# esp.net
KiCad netlist of a schematic drawn in Altium Designer
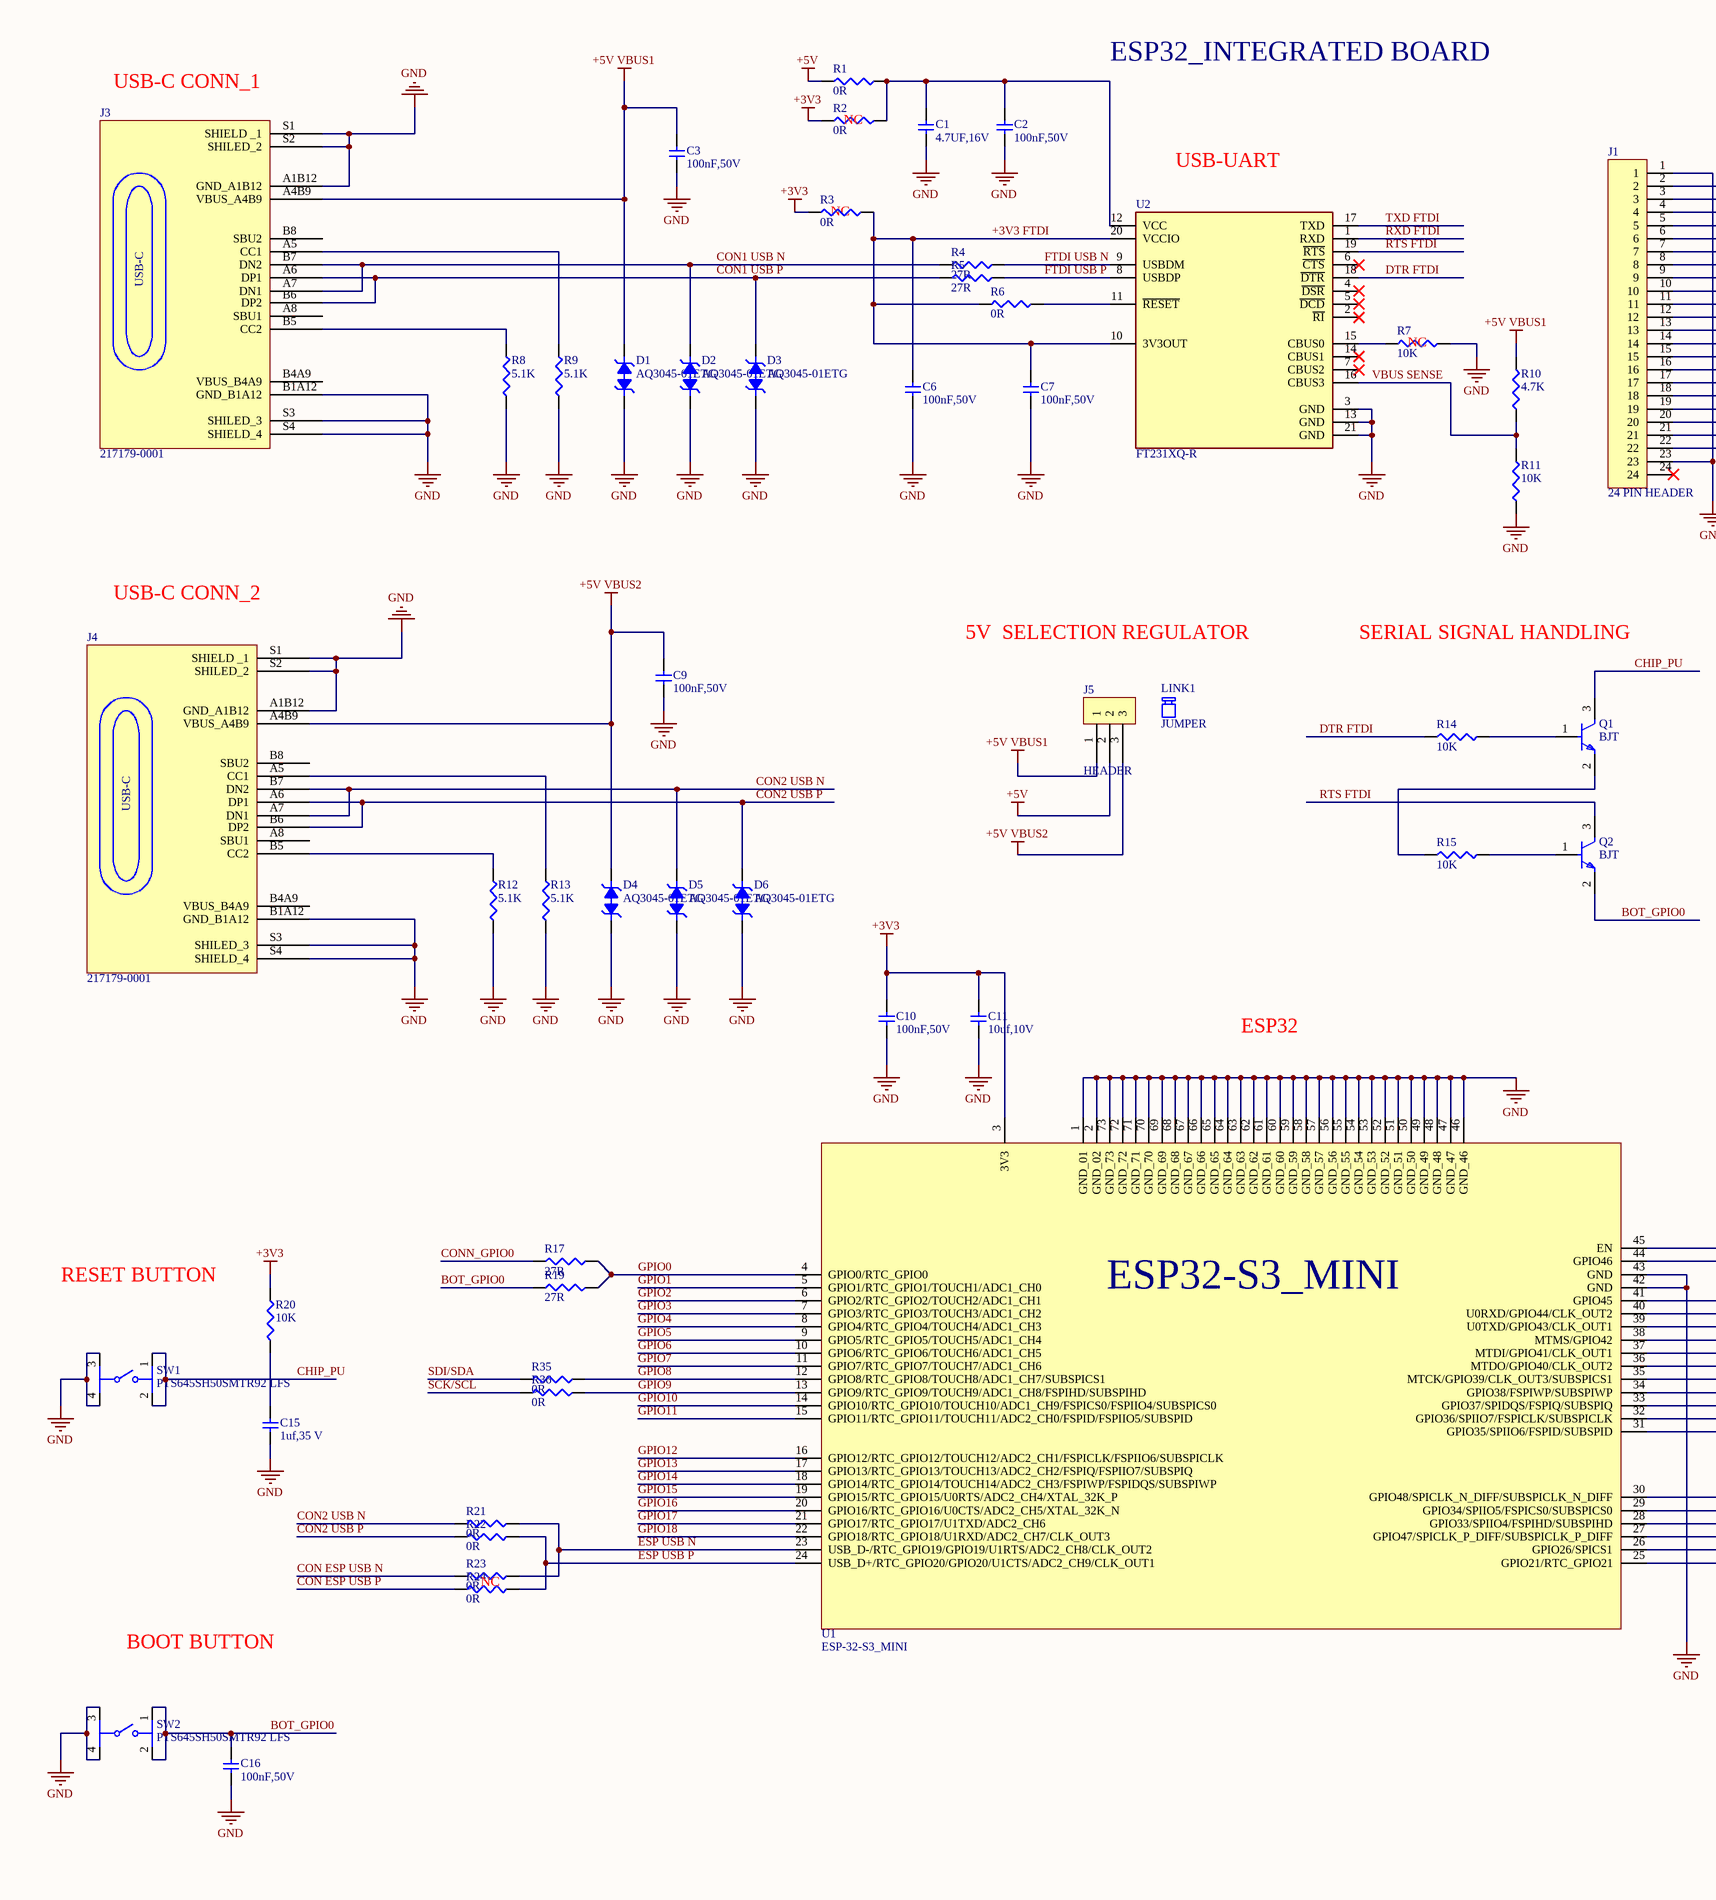
[diagram p0: esp.SchDoc, left]
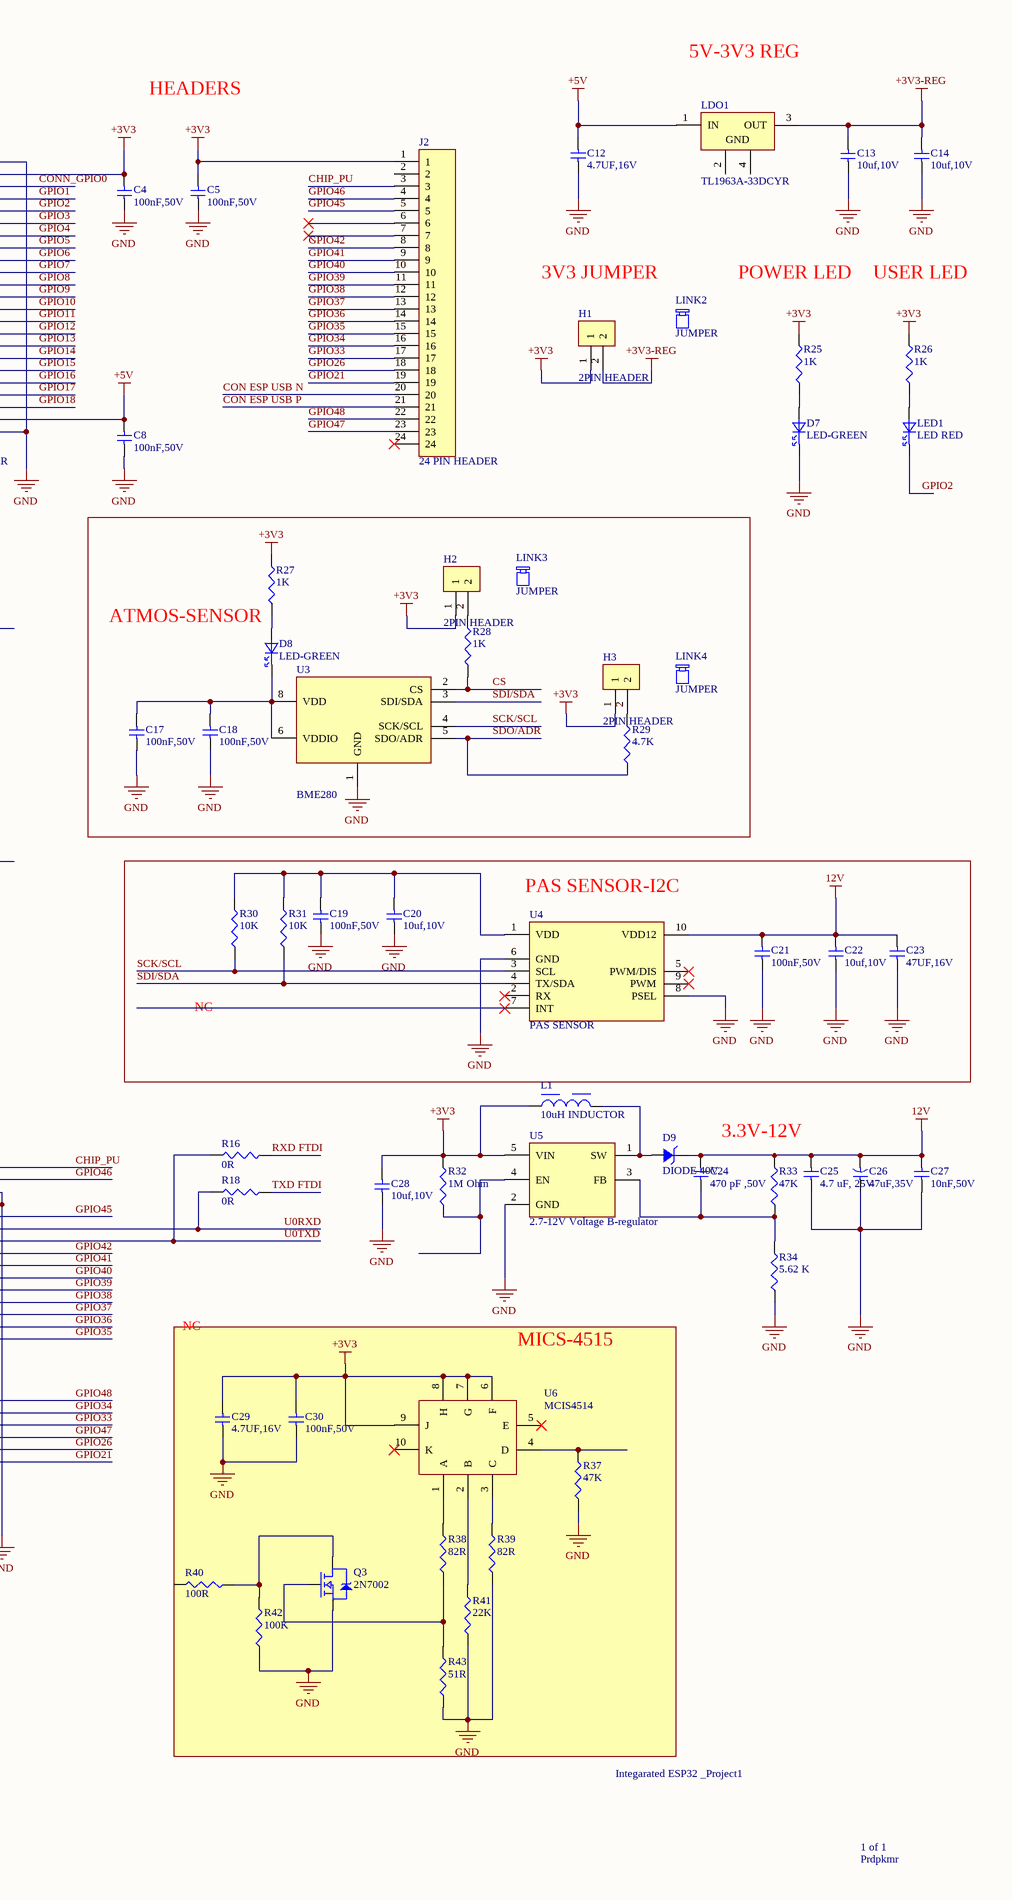
[diagram p1: esp.SchDoc, right]

(export (version "E")
  (design (tool "Eeschema 10.0.6"))
  (components
    (comp (ref "C1")
      (value "4.7UF,16V")
      (footprint "CAPC1005X55N")
      (description "CAP CER 4.7UF 6.3V X5R 0402")
      (fields
        (field (name "MANUFACTURER") "Samsung")
        (field (name "MANUFACTURER PART NUMBER") "CL05A475KQ5NRNC")
      )
      (libsource (lib "Schlib1") (part "CL05A475KQ5NRNC"))
    )
    (comp (ref "C2")
      (value "100nF,50V")
      (footprint "CAPC1005X55N")
      (description "CL05B104KB54PNC")
      (fields (field (name "MANUFACTURER") "Samsung") (field (name "TOLERANCE") "10%"))
      (libsource (lib "Schlib1") (part "CL05B104KB54PNC"))
    )
    (comp (ref "C3")
      (value "100nF,50V")
      (footprint "CAPC1005X55N")
      (description "CL05B104KB54PNC")
      (fields (field (name "MANUFACTURER") "Samsung") (field (name "TOLERANCE") "10%"))
      (libsource (lib "Schlib1") (part "CL05B104KB54PNC"))
    )
    (comp (ref "C4")
      (value "100nF,50V")
      (footprint "CAPC1005X55N")
      (description "CL05B104KB54PNC")
      (fields (field (name "MANUFACTURER") "Samsung") (field (name "TOLERANCE") "10%"))
      (libsource (lib "Schlib1") (part "CL05B104KB54PNC"))
    )
    (comp (ref "C5")
      (value "100nF,50V")
      (footprint "CAPC1005X55N")
      (description "CL05B104KB54PNC")
      (fields (field (name "MANUFACTURER") "Samsung") (field (name "TOLERANCE") "10%"))
      (libsource (lib "Schlib1") (part "CL05B104KB54PNC"))
    )
    (comp (ref "C6")
      (value "100nF,50V")
      (footprint "CAPC1005X55N")
      (description "CL05B104KB54PNC")
      (fields (field (name "MANUFACTURER") "Samsung") (field (name "TOLERANCE") "10%"))
      (libsource (lib "Schlib1") (part "CL05B104KB54PNC"))
    )
    (comp (ref "C7")
      (value "100nF,50V")
      (footprint "CAPC1005X55N")
      (description "CL05B104KB54PNC")
      (fields (field (name "MANUFACTURER") "Samsung") (field (name "TOLERANCE") "10%"))
      (libsource (lib "Schlib1") (part "CL05B104KB54PNC"))
    )
    (comp (ref "C8")
      (value "100nF,50V")
      (footprint "CAPC1005X55N")
      (description "CL05B104KB54PNC")
      (fields (field (name "MANUFACTURER") "Samsung") (field (name "TOLERANCE") "10%"))
      (libsource (lib "Schlib1") (part "CL05B104KB54PNC"))
    )
    (comp (ref "C9")
      (value "100nF,50V")
      (footprint "CAPC1005X55N")
      (description "CL05B104KB54PNC")
      (fields (field (name "MANUFACTURER") "Samsung") (field (name "TOLERANCE") "10%"))
      (libsource (lib "Schlib1") (part "CL05B104KB54PNC"))
    )
    (comp (ref "C10")
      (value "100nF,50V")
      (footprint "CAPC1005X55N")
      (description "CL05B104KB54PNC")
      (fields (field (name "MANUFACTURER") "Samsung") (field (name "TOLERANCE") "10%"))
      (libsource (lib "Schlib1") (part "CL05B104KB54PNC"))
    )
    (comp (ref "C11")
      (value "10uf,10V")
      (footprint "CAPC1005X55N")
      (description "CL05A106MP5NRNC")
      (fields (field (name "MANUFACTURER") "Samsung") (field (name "TOLERANCE") "20%"))
      (libsource (lib "Schlib1") (part "CL05A106MP5NRNC"))
    )
    (comp (ref "C12")
      (value "4.7UF,16V")
      (footprint "CAPC1005X55N")
      (description "CAP CER 4.7UF 6.3V X5R 0402")
      (fields
        (field (name "MANUFACTURER") "Samsung")
        (field (name "MANUFACTURER PART NUMBER") "CL05A475KQ5NRNC")
      )
      (libsource (lib "Schlib1") (part "CL05A475KQ5NRNC"))
    )
    (comp (ref "C13")
      (value "10uf,10V")
      (footprint "CAPC1005X55N")
      (description "CL05A106MP5NRNC")
      (fields (field (name "MANUFACTURER") "Samsung") (field (name "TOLERANCE") "20%"))
      (libsource (lib "Schlib1") (part "CL05A106MP5NRNC"))
    )
    (comp (ref "C14")
      (value "10uf,10V")
      (footprint "CAPC1005X55N")
      (description "CL05A106MP5NRNC")
      (fields (field (name "MANUFACTURER") "Samsung") (field (name "TOLERANCE") "20%"))
      (libsource (lib "Schlib1") (part "CL05A106MP5NRNC"))
    )
    (comp (ref "C15")
      (value "1uf,35 V")
      (footprint "CAPC1005X55N")
      (description "CL05A105KL5NRNC")
      (fields (field (name "MANUFACTURER") "Samsung") (field (name "TOLERANCE") "10%"))
      (libsource (lib "Schlib1") (part "CL05A105KL5NRNC"))
    )
    (comp (ref "C16")
      (value "100nF,50V")
      (footprint "CAPC1005X55N")
      (description "CL05B104KB54PNC")
      (fields (field (name "MANUFACTURER") "Samsung") (field (name "TOLERANCE") "10%"))
      (libsource (lib "Schlib1") (part "CL05B104KB54PNC"))
    )
    (comp (ref "C17")
      (value "100nF,50V")
      (footprint "CAPC1005X55N")
      (description "CL05B104KB54PNC")
      (fields (field (name "MANUFACTURER") "Samsung") (field (name "TOLERANCE") "10%"))
      (libsource (lib "Schlib1") (part "CL05B104KB54PNC"))
    )
    (comp (ref "C18")
      (value "100nF,50V")
      (footprint "CAPC1005X55N")
      (description "CL05B104KB54PNC")
      (fields (field (name "MANUFACTURER") "Samsung") (field (name "TOLERANCE") "10%"))
      (libsource (lib "Schlib1") (part "CL05B104KB54PNC"))
    )
    (comp (ref "C19")
      (value "100nF,50V")
      (footprint "CAPC1005X55N")
      (description "CL05B104KB54PNC")
      (fields (field (name "MANUFACTURER") "Samsung") (field (name "TOLERANCE") "10%"))
      (libsource (lib "Schlib1") (part "CL05B104KB54PNC"))
    )
    (comp (ref "C20")
      (value "10uf,10V")
      (footprint "CAPC1005X55N")
      (description "CL05A106MP5NRNC")
      (fields (field (name "MANUFACTURER") "Samsung") (field (name "TOLERANCE") "20%"))
      (libsource (lib "Schlib1") (part "CL05A106MP5NRNC"))
    )
    (comp (ref "C21")
      (value "100nF,50V")
      (footprint "CAPC1005X55N")
      (description "CL05B104KB54PNC")
      (fields (field (name "MANUFACTURER") "Samsung") (field (name "TOLERANCE") "10%"))
      (libsource (lib "Schlib1") (part "CL05B104KB54PNC"))
    )
    (comp (ref "C22")
      (value "10uf,10V")
      (footprint "CAPC1005X55N")
      (description "CL05A106MP5NRNC")
      (fields (field (name "MANUFACTURER") "Samsung") (field (name "TOLERANCE") "20%"))
      (libsource (lib "Schlib1") (part "CL05A106MP5NRNC"))
    )
    (comp (ref "C23")
      (value "47UF,16V")
      (footprint "CAPC1005X55N")
      (description "CAP TANT 47UF 10% 16V 2917")
      (fields
        (field (name "MANUFACTURER") "KEMET")
        (field (name "MANUFACTURER PART NUMBER") "T499D476K016ATE800")
      )
      (libsource (lib "Schlib1") (part "T499D476K016ATE800"))
    )
    (comp (ref "C24")
      (value "470 pF ,50V")
      (footprint "CAPC1005X55N")
      (description "CAP CER 470PF 50V C0G/NPO 0402")
      (fields
        (field (name "MANUFACTURER") "Yageo")
        (field (name "MANUFACTURER PART NUMBER") "CC0402FRNPO9BN471")
      )
      (libsource (lib "Schlib1") (part "CC0402FRNPO9BN471"))
    )
    (comp (ref "C25")
      (value "4.7 uF, 25V")
      (footprint "CAPC1005X55N")
      (description "Cap Cer 4.7UF 25V X5R 0402")
      (fields
        (field (name "MANUFACTURER") "Kyocera AVX")
        (field (name "MANUFACTURER PART NUMBER") "KGM05CR51E475MH")
      )
      (libsource (lib "Schlib1") (part "KGM05CR51E475MH"))
    )
    (comp (ref "C26")
      (value "47uF,35V")
      (description "CAP TANT 47UF 20% 35V 2917")
      (fields
        (field (name "MANUFACTURER") "KEMET")
        (field (name "MANUFACTURER PART NUMBER") "T495X476M035ATE300")
      )
      (libsource (lib "Schlib1") (part "T495X476M035ATE300"))
    )
    (comp (ref "C27")
      (value "10nF,50V")
      (footprint "CAPC1005X55N")
      (description "CAP CER 0402 10NF 50V X7R 10%")
      (fields
        (field (name "MANUFACTURER") "KEMET")
        (field (name "MANUFACTURER PART NUMBER") "C0402C103K5RECAUTO")
      )
      (libsource (lib "Schlib1") (part "C0402C103K5RECAUTO"))
    )
    (comp (ref "C28")
      (value "10uf,10V")
      (footprint "CAPC1005X55N")
      (description "CL05A106MP5NRNC")
      (fields (field (name "MANUFACTURER") "Samsung") (field (name "TOLERANCE") "20%"))
      (libsource (lib "Schlib1") (part "CL05A106MP5NRNC"))
    )
    (comp (ref "C29")
      (value "4.7UF,16V")
      (footprint "CAPC1005X55N")
      (description "CAP CER 4.7UF 6.3V X5R 0402")
      (fields
        (field (name "MANUFACTURER") "Samsung")
        (field (name "MANUFACTURER PART NUMBER") "CL05A475KQ5NRNC")
      )
      (libsource (lib "Schlib1") (part "CL05A475KQ5NRNC"))
    )
    (comp (ref "C30")
      (value "100nF,50V")
      (footprint "CAPC1005X55N")
      (description "CL05B104KB54PNC")
      (fields (field (name "MANUFACTURER") "Samsung") (field (name "TOLERANCE") "10%"))
      (libsource (lib "Schlib1") (part "CL05B104KB54PNC"))
    )
    (comp (ref "D1")
      (value "AQ3045-01ETG")
      (footprint "DIODFN100X60X50-2N")
      (description "TVS DIODE 5.3VWM 12VC SOD882")
      (fields (field (name "MANUFACTURER") "Littelfuse") (field (name "LCSC PART NUMBER") "C3710326"))
      (libsource (lib "Schlib1") (part "AQ3045-01ETG"))
    )
    (comp (ref "D2")
      (value "AQ3045-01ETG")
      (footprint "DIODFN100X60X50-2N")
      (description "TVS DIODE 5.3VWM 12VC SOD882")
      (fields (field (name "MANUFACTURER") "Littelfuse") (field (name "LCSC PART NUMBER") "C3710326"))
      (libsource (lib "Schlib1") (part "AQ3045-01ETG"))
    )
    (comp (ref "D3")
      (value "AQ3045-01ETG")
      (footprint "DIODFN100X60X50-2N")
      (description "TVS DIODE 5.3VWM 12VC SOD882")
      (fields (field (name "MANUFACTURER") "Littelfuse") (field (name "LCSC PART NUMBER") "C3710326"))
      (libsource (lib "Schlib1") (part "AQ3045-01ETG"))
    )
    (comp (ref "D4")
      (value "AQ3045-01ETG")
      (footprint "DIODFN100X60X50-2N")
      (description "TVS DIODE 5.3VWM 12VC SOD882")
      (fields (field (name "MANUFACTURER") "Littelfuse") (field (name "LCSC PART NUMBER") "C3710326"))
      (libsource (lib "Schlib1") (part "AQ3045-01ETG"))
    )
    (comp (ref "D5")
      (value "AQ3045-01ETG")
      (footprint "DIODFN100X60X50-2N")
      (description "TVS DIODE 5.3VWM 12VC SOD882")
      (fields (field (name "MANUFACTURER") "Littelfuse") (field (name "LCSC PART NUMBER") "C3710326"))
      (libsource (lib "Schlib1") (part "AQ3045-01ETG"))
    )
    (comp (ref "D6")
      (value "AQ3045-01ETG")
      (footprint "DIODFN100X60X50-2N")
      (description "TVS DIODE 5.3VWM 12VC SOD882")
      (fields (field (name "MANUFACTURER") "Littelfuse") (field (name "LCSC PART NUMBER") "C3710326"))
      (libsource (lib "Schlib1") (part "AQ3045-01ETG"))
    )
    (comp (ref "D7")
      (value "LED-GREEN")
      (footprint "LED0402_G")
      (description "LED YLW-GRN 0402 SMD")
      (fields
        (field (name "MANUFACTURER") "Vishay")
        (field (name "MANUFACTURER PART NUMBER") "VLMG1500-GS08")
      )
      (libsource (lib "Schlib1") (part "VLMG1500-GS08"))
    )
    (comp (ref "D8")
      (value "LED-GREEN")
      (footprint "LED0402_G")
      (description "LED YLW-GRN 0402 SMD")
      (fields
        (field (name "MANUFACTURER") "Vishay")
        (field (name "MANUFACTURER PART NUMBER") "VLMG1500-GS08")
      )
      (libsource (lib "Schlib1") (part "VLMG1500-GS08"))
    )
    (comp (ref "D9")
      (value "DIODE 40V")
      (description "TVS DIODE 36VWM 58.1VC DO214AC")
      (fields (field (name "MANUFACTURER") "Yageo") (field (name "MANUFACTURER PART NUMBER") "SMAJ36CA/TR13"))
      (libsource (lib "Schlib1") (part "SMAJ36CA/TR13"))
    )
    (comp (ref "H1")
      (value "2PIN HEADER")
      (footprint "HDR_1X2-1.27MM")
      (description "CONN HEADER VERT 2POS 1.27MM")
      (fields
        (field (name "MANUFACTURER") "Samtec")
        (field (name "MANUFACTURER PART NUMBER") "FTS-102-01-F-S")
      )
      (libsource (lib "Schlib1") (part "FTS-102-01-F-S"))
    )
    (comp (ref "H2")
      (value "2PIN HEADER")
      (footprint "HDR_1X2-1.27MM")
      (description "CONN HEADER VERT 2POS 1.27MM")
      (fields
        (field (name "MANUFACTURER") "Samtec")
        (field (name "MANUFACTURER PART NUMBER") "FTS-102-01-F-S")
      )
      (libsource (lib "Schlib1") (part "FTS-102-01-F-S"))
    )
    (comp (ref "H3")
      (value "2PIN HEADER")
      (footprint "HDR_1X2-1.27MM")
      (description "CONN HEADER VERT 2POS 1.27MM")
      (fields
        (field (name "MANUFACTURER") "Samtec")
        (field (name "MANUFACTURER PART NUMBER") "FTS-102-01-F-S")
      )
      (libsource (lib "Schlib1") (part "FTS-102-01-F-S"))
    )
    (comp (ref "J1")
      (value "24 PIN HEADER")
      (footprint "hdr_1x24")
      (description "CONN HEADER VERT 24POS 2.54MM")
      (fields (field (name "MANUFACTURER") "Molex") (field (name "MANUFACTURER PART NUMBER") "22-28-4245"))
      (libsource (lib "Schlib1") (part "22-28-4245"))
    )
    (comp (ref "J2")
      (value "24 PIN HEADER")
      (footprint "hdr_1x24")
      (description "CONN HEADER VERT 24POS 2.54MM")
      (fields (field (name "MANUFACTURER") "Molex") (field (name "MANUFACTURER PART NUMBER") "22-28-4245"))
      (libsource (lib "") (part "22-28-4245_1"))
    )
    (comp (ref "J3")
      (value "217179-0001")
      (footprint "FP-2171790001-MFG")
      (description "CONN RCP USB2.0 TYP C 24P SMD RA")
      (fields (field (name "MANUFACTURER") "Molex") (field (name "LCSC PART NUMBER") "C3197684"))
      (libsource (lib "Schlib1") (part "217179-0001"))
    )
    (comp (ref "J4")
      (value "217179-0001")
      (footprint "FP-2171790001-MFG")
      (description "CONN RCP USB2.0 TYP C 24P SMD RA")
      (fields (field (name "MANUFACTURER") "Molex") (field (name "LCSC PART NUMBER") "C3197684"))
      (libsource (lib "Schlib1") (part "217179-0001"))
    )
    (comp (ref "J5")
      (value "HEADER")
      (footprint "HDR_1X3_1.27mm")
      (description "CONN HEADER VERT 3POS 1.27MM")
      (fields
        (field (name "MANUFACTURER") "Samtec")
        (field (name "MANUFACTURER PART NUMBER") "FTS-103-01-F-S")
      )
      (libsource (lib "Schlib1") (part "FTS-103-01-F-S"))
    )
    (comp (ref "L1")
      (value "10uH INDUCTOR")
      (footprint "WE-LQS_2010")
      (description "FIXED IND 10UH 500MA 850MOHM SMD")
      (fields
        (field (name "MANUFACTURER") "Wurth Electronics")
        (field (name "MANUFACTURER PART NUMBER") "74404020100")
      )
      (libsource (lib "Schlib1") (part "74404020100"))
    )
    (comp (ref "LDO1")
      (value "TL1963A-33DCYR")
      (footprint "DCY0004A_N")
      (description "IC REG LIN 3.3V 1.5A SOT-223-4")
      (fields (field (name "MANUFACTURER") "Texas Instruments") (field (name "LCSC PART NUMBER") "C181262"))
      (libsource (lib "Schlib1") (part "TL1963A-33DCYR"))
    )
    (comp (ref "LED1")
      (value "LED RED")
      (footprint "LED0402_R")
      (description "LED RED 0402 SMD")
      (fields
        (field (name "MANUFACTURER") "Vishay")
        (field (name "MANUFACTURER PART NUMBER") "VLMS1500-GS08")
      )
      (libsource (lib "Schlib1") (part "VLMS1500-GS08"))
    )
    (comp (ref "LINK1")
      (value "JUMPER")
      (description "CONN SHUNT 1.27MM RED")
      (fields (field (name "MANUFACTURER") "Harwin") (field (name "MANUFACTURER PART NUMBER") "M50-1920005"))
      (libsource (lib "Schlib1") (part "M50-1920005"))
    )
    (comp (ref "LINK2")
      (value "JUMPER")
      (description "CONN SHUNT 1.27MM RED")
      (fields (field (name "MANUFACTURER") "Harwin") (field (name "MANUFACTURER PART NUMBER") "M50-1920005"))
      (libsource (lib "Schlib1") (part "M50-1920005"))
    )
    (comp (ref "LINK3")
      (value "JUMPER")
      (description "CONN SHUNT 1.27MM RED")
      (fields (field (name "MANUFACTURER") "Harwin") (field (name "MANUFACTURER PART NUMBER") "M50-1920005"))
      (libsource (lib "Schlib1") (part "M50-1920005"))
    )
    (comp (ref "LINK4")
      (value "JUMPER")
      (description "CONN SHUNT 1.27MM RED")
      (fields (field (name "MANUFACTURER") "Harwin") (field (name "MANUFACTURER PART NUMBER") "M50-1920005"))
      (libsource (lib "Schlib1") (part "M50-1920005"))
    )
    (comp (ref "Q1")
      (value "BJT")
      (footprint "FP-SS8050-G-IPC_B")
      (description "TRANS NPN 25V 1.5A SOT-23-3")
      (fields (field (name "MANUFACTURER") "Comchip") (field (name "MANUFACTURER PART NUMBER") "SS8050-G"))
      (libsource (lib "Schlib1") (part "SS8050-G"))
    )
    (comp (ref "Q2")
      (value "BJT")
      (footprint "FP-SS8050-G-IPC_B")
      (description "TRANS NPN 25V 1.5A SOT-23-3")
      (fields (field (name "MANUFACTURER") "Comchip") (field (name "MANUFACTURER PART NUMBER") "SS8050-G"))
      (libsource (lib "Schlib1") (part "SS8050-G"))
    )
    (comp (ref "Q3")
      (value "2N7002")
      (footprint "SOT95P240X111-3N")
      (description "MOSFET SOT23 N 60V 5OHM 150C")
      (fields (field (name "MANUFACTURER") "ON Semiconductor / Fairchild") (field (name "VOLTAGE") "60V"))
      (libsource (lib "Schlib1") (part "2N7002"))
    )
    (comp (ref "R1")
      (value "0R")
      (footprint "RESC1005X37N")
      (description "RES 0 OHM JUMPER 1/16W 0402")
      (fields
        (field (name "MANUFACTURER") "Yageo")
        (field (name "MANUFACTURER PART NUMBER") "RC0402JR-070RL")
      )
      (libsource (lib "Schlib1") (part "RC0402JR-070RL"))
    )
    (comp (ref "R2")
      (value "0R")
      (footprint "RESC1005X37N")
      (description "RES 0 OHM JUMPER 1/16W 0402")
      (fields
        (field (name "MANUFACTURER") "Yageo")
        (field (name "MANUFACTURER PART NUMBER") "RC0402JR-070RL")
      )
      (libsource (lib "Schlib1") (part "RC0402JR-070RL"))
    )
    (comp (ref "R3")
      (value "0R")
      (footprint "RESC1005X37N")
      (description "RES 0 OHM JUMPER 1/16W 0402")
      (fields
        (field (name "MANUFACTURER") "Yageo")
        (field (name "MANUFACTURER PART NUMBER") "RC0402JR-070RL")
      )
      (libsource (lib "Schlib1") (part "RC0402JR-070RL"))
    )
    (comp (ref "R4")
      (value "27R")
      (footprint "RESC1005X37N")
      (description "RES 27 OHM 1% 1/16W 0402")
      (fields
        (field (name "MANUFACTURER") "Yageo")
        (field (name "MANUFACTURER PART NUMBER") "RC0402FR-0727RL")
      )
      (libsource (lib "Schlib1") (part "RC0402FR-0727RL"))
    )
    (comp (ref "R5")
      (value "27R")
      (footprint "RESC1005X37N")
      (description "RES 27 OHM 1% 1/16W 0402")
      (fields
        (field (name "MANUFACTURER") "Yageo")
        (field (name "MANUFACTURER PART NUMBER") "RC0402FR-0727RL")
      )
      (libsource (lib "Schlib1") (part "RC0402FR-0727RL"))
    )
    (comp (ref "R6")
      (value "0R")
      (footprint "RESC1005X37N")
      (description "RES 0 OHM JUMPER 1/16W 0402")
      (fields
        (field (name "MANUFACTURER") "Yageo")
        (field (name "MANUFACTURER PART NUMBER") "RC0402JR-070RL")
      )
      (libsource (lib "Schlib1") (part "RC0402JR-070RL"))
    )
    (comp (ref "R7")
      (value "10K")
      (footprint "RESC1005X37N")
      (description "AC0402FR-0710KL")
      (fields (field (name "MANUFACTURER") "Yageo") (field (name "TOLERANCE") "1%"))
      (libsource (lib "Schlib1") (part "AC0402FR-0710KL"))
    )
    (comp (ref "R8")
      (value "5.1K")
      (footprint "RESC1005X37N")
      (description "RES SMD 5.1K OHM 1% 1/16W 0402")
      (fields
        (field (name "MANUFACTURER") "Yageo")
        (field (name "MANUFACTURER PART NUMBER") "AC0402FR-075K1L")
      )
      (libsource (lib "Schlib1") (part "AC0402FR-075K1L"))
    )
    (comp (ref "R9")
      (value "5.1K")
      (footprint "RESC1005X37N")
      (description "RES SMD 5.1K OHM 1% 1/16W 0402")
      (fields
        (field (name "MANUFACTURER") "Yageo")
        (field (name "MANUFACTURER PART NUMBER") "AC0402FR-075K1L")
      )
      (libsource (lib "Schlib1") (part "AC0402FR-075K1L"))
    )
    (comp (ref "R10")
      (value "4.7K")
      (footprint "RESC1005X37N")
      (description "RES 4.7K OHM 1% 1/16W 0402")
      (fields
        (field (name "MANUFACTURER") "Yageo")
        (field (name "MANUFACTURER PART NUMBER") "RC0402FR-074K7L")
      )
      (libsource (lib "Schlib1") (part "RC0402FR-074K7L"))
    )
    (comp (ref "R11")
      (value "10K")
      (footprint "RESC1005X37N")
      (description "AC0402FR-0710KL")
      (fields (field (name "MANUFACTURER") "Yageo") (field (name "TOLERANCE") "1%"))
      (libsource (lib "Schlib1") (part "AC0402FR-0710KL"))
    )
    (comp (ref "R12")
      (value "5.1K")
      (footprint "RESC1005X37N")
      (description "RES SMD 5.1K OHM 1% 1/16W 0402")
      (fields
        (field (name "MANUFACTURER") "Yageo")
        (field (name "MANUFACTURER PART NUMBER") "AC0402FR-075K1L")
      )
      (libsource (lib "Schlib1") (part "AC0402FR-075K1L"))
    )
    (comp (ref "R13")
      (value "5.1K")
      (footprint "RESC1005X37N")
      (description "RES SMD 5.1K OHM 1% 1/16W 0402")
      (fields
        (field (name "MANUFACTURER") "Yageo")
        (field (name "MANUFACTURER PART NUMBER") "AC0402FR-075K1L")
      )
      (libsource (lib "Schlib1") (part "AC0402FR-075K1L"))
    )
    (comp (ref "R14")
      (value "10K")
      (footprint "RESC1005X37N")
      (description "AC0402FR-0710KL")
      (fields (field (name "MANUFACTURER") "Yageo") (field (name "TOLERANCE") "1%"))
      (libsource (lib "Schlib1") (part "AC0402FR-0710KL"))
    )
    (comp (ref "R15")
      (value "10K")
      (footprint "RESC1005X37N")
      (description "AC0402FR-0710KL")
      (fields (field (name "MANUFACTURER") "Yageo") (field (name "TOLERANCE") "1%"))
      (libsource (lib "Schlib1") (part "AC0402FR-0710KL"))
    )
    (comp (ref "R16")
      (value "0R")
      (footprint "RESC1005X37N")
      (description "RES 0 OHM JUMPER 1/16W 0402")
      (fields
        (field (name "MANUFACTURER") "Yageo")
        (field (name "MANUFACTURER PART NUMBER") "RC0402JR-070RL")
      )
      (libsource (lib "Schlib1") (part "RC0402JR-070RL"))
    )
    (comp (ref "R17")
      (value "27R")
      (footprint "RESC1005X37N")
      (description "RES 27 OHM 1% 1/16W 0402")
      (fields
        (field (name "MANUFACTURER") "Yageo")
        (field (name "MANUFACTURER PART NUMBER") "RC0402FR-0727RL")
      )
      (libsource (lib "Schlib1") (part "RC0402FR-0727RL"))
    )
    (comp (ref "R18")
      (value "0R")
      (footprint "RESC1005X37N")
      (description "RES 0 OHM JUMPER 1/16W 0402")
      (fields
        (field (name "MANUFACTURER") "Yageo")
        (field (name "MANUFACTURER PART NUMBER") "RC0402JR-070RL")
      )
      (libsource (lib "Schlib1") (part "RC0402JR-070RL"))
    )
    (comp (ref "R19")
      (value "27R")
      (footprint "RESC1005X37N")
      (description "RES 27 OHM 1% 1/16W 0402")
      (fields
        (field (name "MANUFACTURER") "Yageo")
        (field (name "MANUFACTURER PART NUMBER") "RC0402FR-0727RL")
      )
      (libsource (lib "Schlib1") (part "RC0402FR-0727RL"))
    )
    (comp (ref "R20")
      (value "10K")
      (footprint "RESC1005X37N")
      (description "AC0402FR-0710KL")
      (fields (field (name "MANUFACTURER") "Yageo") (field (name "TOLERANCE") "1%"))
      (libsource (lib "Schlib1") (part "AC0402FR-0710KL"))
    )
    (comp (ref "R21")
      (value "0R")
      (footprint "RESC1005X37N")
      (description "RES 0 OHM JUMPER 1/16W 0402")
      (fields
        (field (name "MANUFACTURER") "Yageo")
        (field (name "MANUFACTURER PART NUMBER") "RC0402JR-070RL")
      )
      (libsource (lib "Schlib1") (part "RC0402JR-070RL"))
    )
    (comp (ref "R22")
      (value "0R")
      (footprint "RESC1005X37N")
      (description "RES 0 OHM JUMPER 1/16W 0402")
      (fields
        (field (name "MANUFACTURER") "Yageo")
        (field (name "MANUFACTURER PART NUMBER") "RC0402JR-070RL")
      )
      (libsource (lib "Schlib1") (part "RC0402JR-070RL"))
    )
    (comp (ref "R23")
      (value "0R")
      (footprint "RESC1005X37N")
      (description "RES 0 OHM JUMPER 1/16W 0402")
      (fields
        (field (name "MANUFACTURER") "Yageo")
        (field (name "MANUFACTURER PART NUMBER") "RC0402JR-070RL")
      )
      (libsource (lib "Schlib1") (part "RC0402JR-070RL"))
    )
    (comp (ref "R24")
      (value "0R")
      (footprint "RESC1005X37N")
      (description "RES 0 OHM JUMPER 1/16W 0402")
      (fields
        (field (name "MANUFACTURER") "Yageo")
        (field (name "MANUFACTURER PART NUMBER") "RC0402JR-070RL")
      )
      (libsource (lib "Schlib1") (part "RC0402JR-070RL"))
    )
    (comp (ref "R25")
      (value "1K")
      (footprint "RESC1005X37N")
      (description "RES SMD 1K OHM 0.1% 1/16W 0402")
      (fields
        (field (name "MANUFACTURER") "Yageo")
        (field (name "MANUFACTURER PART NUMBER") "RT0402BRD071KL")
      )
      (libsource (lib "Schlib1") (part "RT0402BRD071KL"))
    )
    (comp (ref "R26")
      (value "1K")
      (footprint "RESC1005X37N")
      (description "RES SMD 1K OHM 0.1% 1/16W 0402")
      (fields
        (field (name "MANUFACTURER") "Yageo")
        (field (name "MANUFACTURER PART NUMBER") "RT0402BRD071KL")
      )
      (libsource (lib "Schlib1") (part "RT0402BRD071KL"))
    )
    (comp (ref "R27")
      (value "1K")
      (footprint "RESC1005X37N")
      (description "RES SMD 1K OHM 0.1% 1/16W 0402")
      (fields
        (field (name "MANUFACTURER") "Yageo")
        (field (name "MANUFACTURER PART NUMBER") "RT0402BRD071KL")
      )
      (libsource (lib "Schlib1") (part "RT0402BRD071KL"))
    )
    (comp (ref "R28")
      (value "1K")
      (footprint "RESC1005X37N")
      (description "RES SMD 1K OHM 0.1% 1/16W 0402")
      (fields
        (field (name "MANUFACTURER") "Yageo")
        (field (name "MANUFACTURER PART NUMBER") "RT0402BRD071KL")
      )
      (libsource (lib "Schlib1") (part "RT0402BRD071KL"))
    )
    (comp (ref "R29")
      (value "4.7K")
      (footprint "RESC1005X37N")
      (description "RES 4.7K OHM 1% 1/16W 0402")
      (fields
        (field (name "MANUFACTURER") "Yageo")
        (field (name "MANUFACTURER PART NUMBER") "RC0402FR-074K7L")
      )
      (libsource (lib "Schlib1") (part "RC0402FR-074K7L"))
    )
    (comp (ref "R30")
      (value "10K")
      (footprint "RESC1005X37N")
      (description "AC0402FR-0710KL")
      (fields (field (name "MANUFACTURER") "Yageo") (field (name "TOLERANCE") "1%"))
      (libsource (lib "Schlib1") (part "AC0402FR-0710KL"))
    )
    (comp (ref "R31")
      (value "10K")
      (footprint "RESC1005X37N")
      (description "AC0402FR-0710KL")
      (fields (field (name "MANUFACTURER") "Yageo") (field (name "TOLERANCE") "1%"))
      (libsource (lib "Schlib1") (part "AC0402FR-0710KL"))
    )
    (comp (ref "R32")
      (value "1M Ohm")
      (footprint "RESC1005X37N")
      (description "Thick Film Resistors 1 MOhms 1/16W 0402 0.1%")
      (fields
        (field (name "MANUFACTURER") "Yageo")
        (field (name "MANUFACTURER PART NUMBER") "RC0402BR-071ML")
      )
      (libsource (lib "Schlib1") (part "RC0402BR-071ML"))
    )
    (comp (ref "R33")
      (value "47K")
      (footprint "RESC1005X37N")
      (description "RES SMD 47K OHM 0.1% 1/16W 0402")
      (fields
        (field (name "MANUFACTURER") "Yageo")
        (field (name "MANUFACTURER PART NUMBER") "RT0402BRD0747KL")
      )
      (libsource (lib "Schlib1") (part "RT0402BRD0747KL"))
    )
    (comp (ref "R34")
      (value "5.62 K")
      (footprint "RESC1005X37N")
      (description "RES 5.62K OHM 1% 1/16W 0402")
      (fields
        (field (name "MANUFACTURER") "Yageo")
        (field (name "MANUFACTURER PART NUMBER") "RC0402FR-075K62L")
      )
      (libsource (lib "Schlib1") (part "RC0402FR-075K62L"))
    )
    (comp (ref "R35")
      (value "0R")
      (footprint "RESC1005X37N")
      (description "RES 0 OHM JUMPER 1/16W 0402")
      (fields
        (field (name "MANUFACTURER") "Yageo")
        (field (name "MANUFACTURER PART NUMBER") "RC0402JR-070RL")
      )
      (libsource (lib "Schlib1") (part "RC0402JR-070RL"))
    )
    (comp (ref "R36")
      (value "0R")
      (footprint "RESC1005X37N")
      (description "RES 0 OHM JUMPER 1/16W 0402")
      (fields
        (field (name "MANUFACTURER") "Yageo")
        (field (name "MANUFACTURER PART NUMBER") "RC0402JR-070RL")
      )
      (libsource (lib "Schlib1") (part "RC0402JR-070RL"))
    )
    (comp (ref "R37")
      (value "47K")
      (footprint "RESC1005X37N")
      (description "RES SMD 47K OHM 0.1% 1/16W 0402")
      (fields
        (field (name "MANUFACTURER") "Yageo")
        (field (name "MANUFACTURER PART NUMBER") "RT0402BRD0747KL")
      )
      (libsource (lib "Schlib1") (part "RT0402BRD0747KL"))
    )
    (comp (ref "R38")
      (value "82R")
      (footprint "RESC1005X37N")
      (description "RES SMD 82 OHM 0.5% 1/16W 0402")
      (fields
        (field (name "MANUFACTURER") "Yageo")
        (field (name "MANUFACTURER PART NUMBER") "RT0402DRE0782RL")
      )
      (libsource (lib "Schlib1") (part "RT0402DRE0782RL"))
    )
    (comp (ref "R39")
      (value "82R")
      (footprint "RESC1005X37N")
      (description "RES SMD 82 OHM 0.5% 1/16W 0402")
      (fields
        (field (name "MANUFACTURER") "Yageo")
        (field (name "MANUFACTURER PART NUMBER") "RT0402DRE0782RL")
      )
      (libsource (lib "Schlib1") (part "RT0402DRE0782RL"))
    )
    (comp (ref "R40")
      (value "100R")
      (footprint "RESC1005X37N")
      (description "RES 100 OHM 1% 1/8W 0402")
      (fields
        (field (name "MANUFACTURER") "Yageo")
        (field (name "MANUFACTURER PART NUMBER") "RC0402FR-7W100RL")
      )
      (libsource (lib "Schlib1") (part "RC0402FR-7W100RL"))
    )
    (comp (ref "R41")
      (value "22K")
      (footprint "RESC1005X37N")
      (description "RES 22K OHM 1% 1/16W 0402")
      (fields
        (field (name "MANUFACTURER") "TE Connectivity")
        (field (name "MANUFACTURER PART NUMBER") "CRGCQ0402F22K")
      )
      (libsource (lib "Schlib1") (part "CRGCQ0402F22K"))
    )
    (comp (ref "R42")
      (value "100K")
      (footprint "RESC1005X37N")
      (description "RES 100K OHM 1% 1/8W 0402")
      (fields
        (field (name "MANUFACTURER") "Yageo")
        (field (name "MANUFACTURER PART NUMBER") "RC0402FR-7W100KL")
      )
      (libsource (lib "Schlib1") (part "RC0402FR-7W100KL"))
    )
    (comp (ref "R43")
      (value "51R")
      (footprint "RESC1005X37N")
      (description "RES SMD 51 OHM 0.5% 1/16W 0402")
      (fields
        (field (name "MANUFACTURER") "Yageo")
        (field (name "MANUFACTURER PART NUMBER") "RT0402DRE0751RL")
      )
      (libsource (lib "Schlib1") (part "RT0402DRE0751RL"))
    )
    (comp (ref "SW1")
      (value "PTS645SH50SMTR92 LFS")
      (footprint "FP-PTS645SH50SMTR92LFS-MFG")
      (description "SWITCH TACTILE SPST-NO 0.05A 12V")
      (fields
        (field (name "MANUFACTURER") "ITT C&K")
        (field (name "MANUFACTURER PART NUMBER") "PTS645SH50SMTR92LFS")
      )
      (libsource (lib "Schlib1") (part "PTS645SH50SMTR92LFS"))
    )
    (comp (ref "SW2")
      (value "PTS645SH50SMTR92 LFS")
      (footprint "FP-PTS645SH50SMTR92LFS-MFG")
      (description "SWITCH TACTILE SPST-NO 0.05A 12V")
      (fields
        (field (name "MANUFACTURER") "ITT C&K")
        (field (name "MANUFACTURER PART NUMBER") "PTS645SH50SMTR92LFS")
      )
      (libsource (lib "Schlib1") (part "PTS645SH50SMTR92LFS"))
    )
    (comp (ref "U1")
      (value "ESP-32-S3_MINI")
      (footprint "XCVR_ESP32-S3-MINI-1-N8")
      (description "20.5dBm ESP32-S3FN8 Chip 2.4GHz SMD WiFi Modules ROHS")
      (fields
        (field (name "MANUFACTURER") "Espressif Systems")
        (field (name "MANUFACTURER PART NUMBER") "ESP32-S3-MINI-1-N8")
      )
      (libsource (lib "Schlib1") (part "ESP32-S3-MINI-1-N8"))
    )
    (comp (ref "U2")
      (value "FT231XQ-R")
      (footprint "FP-QFN-20-IPC_B")
      (description "IC USB SERIAL FULL UART 20QFN")
      (fields (field (name "MANUFACTURER") "FTDI") (field (name "LCSC PART NUMBER") "C132159"))
      (libsource (lib "Schlib1") (part "FT231XQ-R"))
    )
    (comp (ref "U3")
      (value "BME280")
      (footprint "PSON65P250X250X100-8N")
      (description "SENSOR PRESSURE HUMIDITY TEMP")
      (fields (field (name "MANUFACTURER") "Bosch Tools") (field (name "LCSC PART NUMBER") "C92489"))
      (libsource (lib "Schlib1") (part "BME280"))
    )
    (comp (ref "U4")
      (value "PAS SENSOR")
      (footprint "PQFN50P300X300X80-16N")
      (description "SENSOR CARBON DIOXIDE I2C OUTPUT")
      (fields
        (field (name "MANUFACTURER") "Infineon")
        (field (name "MANUFACTURER PART NUMBER") "PASCO2V01BUMA1")
      )
      (libsource (lib "Schlib1") (part "PASCO2V01BUMA1"))
    )
    (comp (ref "U5")
      (value "2.7-12V Voltage B-regulator")
      (footprint "SOT95P280X145-5N")
      (description "IC REG BST SEPIC ADJ 2.1A SOT23")
      (fields
        (field (name "MANUFACTURER") "TI National Semiconductor")
        (field (name "MANUFACTURER PART NUMBER") "LMR62421XMFX/NOPB")
      )
      (libsource (lib "Schlib1") (part "LMR62421XMFX/NOPB"))
    )
    (comp (ref "U6")
      (value "MCIS4514")
      (description "SENSOR CARBON MONOXIDE")
      (fields
        (field (name "MANUFACTURER") "SGX Sensortech")
        (field (name "MANUFACTURER PART NUMBER") "MICS-4514")
      )
      (libsource (lib "Schlib1") (part "MICS-4514"))
    )
  )
  (nets
    (net (code "1") (name "+3V3") (class "Default")
      (node (ref "C10") (pin "2") (pinfunction "_2_2") (pintype "passive"))
      (node (ref "C11") (pin "2") (pinfunction "_2_2") (pintype "passive"))
      (node (ref "C28") (pin "2") (pinfunction "_2_2") (pintype "passive"))
      (node (ref "C29") (pin "2") (pinfunction "_2_2") (pintype "passive"))
      (node (ref "C30") (pin "2") (pinfunction "_2_2") (pintype "passive"))
      (node (ref "C4") (pin "2") (pinfunction "_2_2") (pintype "passive"))
      (node (ref "C5") (pin "2") (pinfunction "_2_2") (pintype "passive"))
      (node (ref "H1") (pin "1") (pinfunction "1_1") (pintype "passive"))
      (node (ref "H2") (pin "1") (pinfunction "1_1") (pintype "passive"))
      (node (ref "H3") (pin "1") (pinfunction "1_1") (pintype "passive"))
      (node (ref "J1") (pin "2") (pinfunction "2_2") (pintype "passive"))
      (node (ref "J2") (pin "1") (pinfunction "1_1") (pintype "passive"))
      (node (ref "L1") (pin "1") (pinfunction "1_1") (pintype "passive"))
      (node (ref "R2") (pin "2") (pinfunction "2_2") (pintype "passive"))
      (node (ref "R20") (pin "1") (pinfunction "1_1") (pintype "passive"))
      (node (ref "R25") (pin "2") (pinfunction "2_2") (pintype "passive"))
      (node (ref "R26") (pin "2") (pinfunction "2_2") (pintype "passive"))
      (node (ref "R27") (pin "2") (pinfunction "2_2") (pintype "passive"))
      (node (ref "R3") (pin "2") (pinfunction "2_2") (pintype "passive"))
      (node (ref "R32") (pin "2") (pinfunction "2_2") (pintype "passive"))
      (node (ref "U1") (pin "3") (pinfunction "3V3_3") (pintype "passive"))
      (node (ref "U5") (pin "5") (pinfunction "VIN_5") (pintype "passive"))
      (node (ref "U6") (pin "6") (pinfunction "F_6") (pintype "passive"))
      (node (ref "U6") (pin "7") (pinfunction "G_7") (pintype "passive"))
      (node (ref "U6") (pin "8") (pinfunction "H_8") (pintype "passive"))
      (node (ref "U6") (pin "9") (pinfunction "J_9") (pintype "passive"))
    )
    (net (code "2") (name "+3V3-REG") (class "Default")
      (node (ref "C13") (pin "2") (pinfunction "_2_2") (pintype "passive"))
      (node (ref "C14") (pin "2") (pinfunction "_2_2") (pintype "passive"))
      (node (ref "H1") (pin "2") (pinfunction "2_2") (pintype "passive"))
      (node (ref "LDO1") (pin "3") (pinfunction "OUT_3") (pintype "power_in"))
    )
    (net (code "3") (name "+5V") (class "Default")
      (node (ref "C12") (pin "1") (pinfunction "1_1") (pintype "passive"))
      (node (ref "C8") (pin "2") (pinfunction "_2_2") (pintype "passive"))
      (node (ref "J1") (pin "22") (pinfunction "22_22") (pintype "passive"))
      (node (ref "J5") (pin "2") (pinfunction "2_2") (pintype "passive"))
      (node (ref "LDO1") (pin "1") (pinfunction "IN_1") (pintype "power_in"))
      (node (ref "R1") (pin "2") (pinfunction "2_2") (pintype "passive"))
    )
    (net (code "4") (name "+5V VBUS1") (class "Default")
      (node (ref "C3") (pin "2") (pinfunction "_2_2") (pintype "passive"))
      (node (ref "D1") (pin "1") (pinfunction "1_1") (pintype "passive"))
      (node (ref "J3") (pin "A4B9") (pinfunction "VBUS_A4B9_A4B9") (pintype "passive"))
      (node (ref "J5") (pin "1") (pinfunction "1_1") (pintype "passive"))
      (node (ref "R10") (pin "2") (pinfunction "2_2") (pintype "passive"))
    )
    (net (code "5") (name "+5V VBUS2") (class "Default")
      (node (ref "C9") (pin "2") (pinfunction "_2_2") (pintype "passive"))
      (node (ref "D4") (pin "1") (pinfunction "1_1") (pintype "passive"))
      (node (ref "J4") (pin "A4B9") (pinfunction "VBUS_A4B9_A4B9") (pintype "passive"))
      (node (ref "J5") (pin "3") (pinfunction "3_3") (pintype "passive"))
    )
    (net (code "6") (name "/+3V3 FTDI") (class "Default")
      (node (ref "C6") (pin "2") (pinfunction "_2_2") (pintype "passive"))
      (node (ref "C7") (pin "2") (pinfunction "_2_2") (pintype "passive"))
      (node (ref "R3") (pin "1") (pinfunction "1_1") (pintype "passive"))
      (node (ref "R6") (pin "2") (pinfunction "2_2") (pintype "passive"))
      (node (ref "U2") (pin "10") (pinfunction "3V3OUT_10") (pintype "passive"))
      (node (ref "U2") (pin "20") (pinfunction "VCCIO_20") (pintype "passive"))
    )
    (net (code "7") (name "/BOT_GPIO0") (class "Default")
      (node (ref "C16") (pin "2") (pinfunction "_2_2") (pintype "passive"))
      (node (ref "Q2") (pin "2") (pinfunction "E_2") (pintype "passive"))
      (node (ref "R19") (pin "1") (pinfunction "1_1") (pintype "passive"))
      (node (ref "SW2") (pin "1") (pinfunction "1_1") (pintype "passive"))
      (node (ref "SW2") (pin "2") (pinfunction "2_2") (pintype "passive"))
    )
    (net (code "8") (name "/CHIP_PU") (class "Default")
      (node (ref "J2") (pin "3") (pinfunction "3_3") (pintype "passive"))
      (node (ref "Q1") (pin "3") (pinfunction "C_3") (pintype "passive"))
      (node (ref "SW1") (pin "1") (pinfunction "1_1") (pintype "passive"))
      (node (ref "SW1") (pin "2") (pinfunction "2_2") (pintype "passive"))
      (node (ref "U1") (pin "45") (pinfunction "EN_45") (pintype "passive"))
    )
    (net (code "9") (name "/CON ESP USB N") (class "Default")
      (node (ref "J2") (pin "20") (pinfunction "20_20") (pintype "passive"))
      (node (ref "R23") (pin "2") (pinfunction "2_2") (pintype "passive"))
    )
    (net (code "10") (name "/CON ESP USB P") (class "Default")
      (node (ref "J2") (pin "21") (pinfunction "21_21") (pintype "passive"))
      (node (ref "R24") (pin "2") (pinfunction "2_2") (pintype "passive"))
    )
    (net (code "11") (name "/CON1 USB N") (class "Default")
      (node (ref "D2") (pin "1") (pinfunction "1_1") (pintype "passive"))
      (node (ref "J3") (pin "A7") (pinfunction "DN1_A7") (pintype "passive"))
      (node (ref "J3") (pin "B7") (pinfunction "DN2_B7") (pintype "passive"))
      (node (ref "R4") (pin "1") (pinfunction "1_1") (pintype "passive"))
    )
    (net (code "12") (name "/CON1 USB P") (class "Default")
      (node (ref "D3") (pin "1") (pinfunction "1_1") (pintype "passive"))
      (node (ref "J3") (pin "A6") (pinfunction "DP1_A6") (pintype "passive"))
      (node (ref "J3") (pin "B6") (pinfunction "DP2_B6") (pintype "passive"))
      (node (ref "R5") (pin "1") (pinfunction "1_1") (pintype "passive"))
    )
    (net (code "13") (name "/CON2 USB N") (class "Default")
      (node (ref "D5") (pin "1") (pinfunction "1_1") (pintype "passive"))
      (node (ref "J4") (pin "A7") (pinfunction "DN1_A7") (pintype "passive"))
      (node (ref "J4") (pin "B7") (pinfunction "DN2_B7") (pintype "passive"))
      (node (ref "R21") (pin "2") (pinfunction "2_2") (pintype "passive"))
    )
    (net (code "14") (name "/CON2 USB P") (class "Default")
      (node (ref "D6") (pin "1") (pinfunction "1_1") (pintype "passive"))
      (node (ref "J4") (pin "A6") (pinfunction "DP1_A6") (pintype "passive"))
      (node (ref "J4") (pin "B6") (pinfunction "DP2_B6") (pintype "passive"))
      (node (ref "R22") (pin "2") (pinfunction "2_2") (pintype "passive"))
    )
    (net (code "15") (name "/CONN_GPIO0") (class "Default")
      (node (ref "J1") (pin "3") (pinfunction "3_3") (pintype "passive"))
      (node (ref "R17") (pin "1") (pinfunction "1_1") (pintype "passive"))
    )
    (net (code "16") (name "/CS") (class "Default")
      (node (ref "R28") (pin "2") (pinfunction "2_2") (pintype "passive"))
      (node (ref "U3") (pin "2") (pinfunction "CS_2") (pintype "passive"))
    )
    (net (code "17") (name "/DTR FTDI") (class "Default")
      (node (ref "R14") (pin "1") (pinfunction "1_1") (pintype "passive"))
      (node (ref "U2") (pin "18") (pinfunction "~{DTR}_18") (pintype "passive"))
    )
    (net (code "18") (name "/ESP USB N") (class "Default")
      (node (ref "R21") (pin "1") (pinfunction "1_1") (pintype "passive"))
      (node (ref "R23") (pin "1") (pinfunction "1_1") (pintype "passive"))
      (node (ref "U1") (pin "23") (pinfunction "USB_D-/RTC_GPIO19/GPIO19/U1RTS/ADC2_CH8/CLK_OUT2_23") (pintype "passive"))
    )
    (net (code "19") (name "/ESP USB P") (class "Default")
      (node (ref "R22") (pin "1") (pinfunction "1_1") (pintype "passive"))
      (node (ref "R24") (pin "1") (pinfunction "1_1") (pintype "passive"))
      (node (ref "U1") (pin "24") (pinfunction "USB_D+/RTC_GPIO20/GPIO20/U1CTS/ADC2_CH9/CLK_OUT1_24") (pintype "passive"))
    )
    (net (code "20") (name "/FTDI USB N") (class "Default")
      (node (ref "R4") (pin "2") (pinfunction "2_2") (pintype "passive"))
      (node (ref "U2") (pin "9") (pinfunction "USBDM_9") (pintype "passive"))
    )
    (net (code "21") (name "/FTDI USB P") (class "Default")
      (node (ref "R5") (pin "2") (pinfunction "2_2") (pintype "passive"))
      (node (ref "U2") (pin "8") (pinfunction "USBDP_8") (pintype "passive"))
    )
    (net (code "22") (name "/GPIO0") (class "Default")
      (node (ref "R17") (pin "2") (pinfunction "2_2") (pintype "passive"))
      (node (ref "R19") (pin "2") (pinfunction "2_2") (pintype "passive"))
      (node (ref "U1") (pin "4") (pinfunction "GPIO0/RTC_GPIO0_4") (pintype "passive"))
    )
    (net (code "23") (name "/GPIO1") (class "Default")
      (node (ref "J1") (pin "4") (pinfunction "4_4") (pintype "passive"))
      (node (ref "U1") (pin "5") (pinfunction "GPIO1/RTC_GPIO1/TOUCH1/ADC1_CH0_5") (pintype "passive"))
    )
    (net (code "24") (name "/GPIO2") (class "Default")
      (node (ref "J1") (pin "5") (pinfunction "5_5") (pintype "passive"))
      (node (ref "LED1") (pin "1") (pinfunction "1_1") (pintype "passive"))
      (node (ref "U1") (pin "6") (pinfunction "GPIO2/RTC_GPIO2/TOUCH2/ADC1_CH1_6") (pintype "passive"))
    )
    (net (code "25") (name "/GPIO3") (class "Default")
      (node (ref "J1") (pin "6") (pinfunction "6_6") (pintype "passive"))
      (node (ref "U1") (pin "7") (pinfunction "GPIO3/RTC_GPIO3/TOUCH3/ADC1_CH2_7") (pintype "passive"))
    )
    (net (code "26") (name "/GPIO4") (class "Default")
      (node (ref "J1") (pin "7") (pinfunction "7_7") (pintype "passive"))
      (node (ref "U1") (pin "8") (pinfunction "GPIO4/RTC_GPIO4/TOUCH4/ADC1_CH3_8") (pintype "passive"))
    )
    (net (code "27") (name "/GPIO5") (class "Default")
      (node (ref "J1") (pin "8") (pinfunction "8_8") (pintype "passive"))
      (node (ref "U1") (pin "9") (pinfunction "GPIO5/RTC_GPIO5/TOUCH5/ADC1_CH4_9") (pintype "passive"))
    )
    (net (code "28") (name "/GPIO6") (class "Default")
      (node (ref "J1") (pin "9") (pinfunction "9_9") (pintype "passive"))
      (node (ref "U1") (pin "10") (pinfunction "GPIO6/RTC_GPIO6/TOUCH6/ADC1_CH5_10") (pintype "passive"))
    )
    (net (code "29") (name "/GPIO7") (class "Default")
      (node (ref "J1") (pin "10") (pinfunction "10_10") (pintype "passive"))
      (node (ref "U1") (pin "11") (pinfunction "GPIO7/RTC_GPIO7/TOUCH7/ADC1_CH6_11") (pintype "passive"))
    )
    (net (code "30") (name "/GPIO8") (class "Default")
      (node (ref "J1") (pin "11") (pinfunction "11_11") (pintype "passive"))
      (node (ref "R35") (pin "1") (pinfunction "1_1") (pintype "passive"))
      (node (ref "U1") (pin "12") (pinfunction "GPIO8/RTC_GPIO8/TOUCH8/ADC1_CH7/SUBSPICS1_12") (pintype "passive"))
    )
    (net (code "31") (name "/GPIO9") (class "Default")
      (node (ref "J1") (pin "12") (pinfunction "12_12") (pintype "passive"))
      (node (ref "R36") (pin "1") (pinfunction "1_1") (pintype "passive"))
      (node (ref "U1") (pin "13") (pinfunction "GPIO9/RTC_GPIO9/TOUCH9/ADC1_CH8/FSPIHD/SUBSPIHD_13") (pintype "passive"))
    )
    (net (code "32") (name "/GPIO10") (class "Default")
      (node (ref "J1") (pin "13") (pinfunction "13_13") (pintype "passive"))
      (node (ref "U1") (pin "14") (pinfunction "GPIO10/RTC_GPIO10/TOUCH10/ADC1_CH9/FSPICS0/FSPIIO4/SUBSPICS0_14") (pintype "passive"))
    )
    (net (code "33") (name "/GPIO11") (class "Default")
      (node (ref "J1") (pin "14") (pinfunction "14_14") (pintype "passive"))
      (node (ref "U1") (pin "15") (pinfunction "GPIO11/RTC_GPIO11/TOUCH11/ADC2_CH0/FSPID/FSPIIO5/SUBSPID_15") (pintype "passive"))
    )
    (net (code "34") (name "/GPIO12") (class "Default")
      (node (ref "J1") (pin "15") (pinfunction "15_15") (pintype "passive"))
      (node (ref "U1") (pin "16") (pinfunction "GPIO12/RTC_GPIO12/TOUCH12/ADC2_CH1/FSPICLK/FSPIIO6/SUBSPICLK_16") (pintype "passive"))
    )
    (net (code "35") (name "/GPIO13") (class "Default")
      (node (ref "J1") (pin "16") (pinfunction "16_16") (pintype "passive"))
      (node (ref "U1") (pin "17") (pinfunction "GPIO13/RTC_GPIO13/TOUCH13/ADC2_CH2/FSPIQ/FSPIIO7/SUBSPIQ_17") (pintype "passive"))
    )
    (net (code "36") (name "/GPIO14") (class "Default")
      (node (ref "J1") (pin "17") (pinfunction "17_17") (pintype "passive"))
      (node (ref "U1") (pin "18") (pinfunction "GPIO14/RTC_GPIO14/TOUCH14/ADC2_CH3/FSPIWP/FSPIDQS/SUBSPIWP_18") (pintype "passive"))
    )
    (net (code "37") (name "/GPIO15") (class "Default")
      (node (ref "J1") (pin "18") (pinfunction "18_18") (pintype "passive"))
      (node (ref "U1") (pin "19") (pinfunction "GPIO15/RTC_GPIO15/U0RTS/ADC2_CH4/XTAL_32K_P_19") (pintype "passive"))
    )
    (net (code "38") (name "/GPIO16") (class "Default")
      (node (ref "J1") (pin "19") (pinfunction "19_19") (pintype "passive"))
      (node (ref "U1") (pin "20") (pinfunction "GPIO16/RTC_GPIO16/U0CTS/ADC2_CH5/XTAL_32K_N_20") (pintype "passive"))
    )
    (net (code "39") (name "/GPIO17") (class "Default")
      (node (ref "J1") (pin "20") (pinfunction "20_20") (pintype "passive"))
      (node (ref "U1") (pin "21") (pinfunction "GPIO17/RTC_GPIO17/U1TXD/ADC2_CH6_21") (pintype "passive"))
    )
    (net (code "40") (name "/GPIO18") (class "Default")
      (node (ref "J1") (pin "21") (pinfunction "21_21") (pintype "passive"))
      (node (ref "U1") (pin "22") (pinfunction "GPIO18/RTC_GPIO18/U1RXD/ADC2_CH7/CLK_OUT3_22") (pintype "passive"))
    )
    (net (code "41") (name "/GPIO21") (class "Default")
      (node (ref "J2") (pin "19") (pinfunction "19_19") (pintype "passive"))
      (node (ref "U1") (pin "25") (pinfunction "GPIO21/RTC_GPIO21_25") (pintype "passive"))
    )
    (net (code "42") (name "/GPIO26") (class "Default")
      (node (ref "J2") (pin "18") (pinfunction "18_18") (pintype "passive"))
      (node (ref "U1") (pin "26") (pinfunction "GPIO26/SPICS1_26") (pintype "passive"))
    )
    (net (code "43") (name "/GPIO33") (class "Default")
      (node (ref "J2") (pin "17") (pinfunction "17_17") (pintype "passive"))
      (node (ref "U1") (pin "28") (pinfunction "GPIO33/SPIIO4/FSPIHD/SUBSPIHD_28") (pintype "passive"))
    )
    (net (code "44") (name "/GPIO34") (class "Default")
      (node (ref "J2") (pin "16") (pinfunction "16_16") (pintype "passive"))
      (node (ref "U1") (pin "29") (pinfunction "GPIO34/SPIIO5/FSPICS0/SUBSPICS0_29") (pintype "passive"))
    )
    (net (code "45") (name "/GPIO35") (class "Default")
      (node (ref "J2") (pin "15") (pinfunction "15_15") (pintype "passive"))
      (node (ref "U1") (pin "31") (pinfunction "GPIO35/SPIIO6/FSPID/SUBSPID_31") (pintype "passive"))
    )
    (net (code "46") (name "/GPIO36") (class "Default")
      (node (ref "J2") (pin "14") (pinfunction "14_14") (pintype "passive"))
      (node (ref "U1") (pin "32") (pinfunction "GPIO36/SPIIO7/FSPICLK/SUBSPICLK_32") (pintype "passive"))
    )
    (net (code "47") (name "/GPIO37") (class "Default")
      (node (ref "J2") (pin "13") (pinfunction "13_13") (pintype "passive"))
      (node (ref "U1") (pin "33") (pinfunction "GPIO37/SPIDQS/FSPIQ/SUBSPIQ_33") (pintype "passive"))
    )
    (net (code "48") (name "/GPIO38") (class "Default")
      (node (ref "J2") (pin "12") (pinfunction "12_12") (pintype "passive"))
      (node (ref "U1") (pin "34") (pinfunction "GPIO38/FSPIWP/SUBSPIWP_34") (pintype "passive"))
    )
    (net (code "49") (name "/GPIO39") (class "Default")
      (node (ref "J2") (pin "11") (pinfunction "11_11") (pintype "passive"))
      (node (ref "U1") (pin "35") (pinfunction "MTCK/GPIO39/CLK_OUT3/SUBSPICS1_35") (pintype "passive"))
    )
    (net (code "50") (name "/GPIO40") (class "Default")
      (node (ref "J2") (pin "10") (pinfunction "10_10") (pintype "passive"))
      (node (ref "U1") (pin "36") (pinfunction "MTDO/GPIO40/CLK_OUT2_36") (pintype "passive"))
    )
    (net (code "51") (name "/GPIO41") (class "Default")
      (node (ref "J2") (pin "9") (pinfunction "9_9") (pintype "passive"))
      (node (ref "U1") (pin "37") (pinfunction "MTDI/GPIO41/CLK_OUT1_37") (pintype "passive"))
    )
    (net (code "52") (name "/GPIO42") (class "Default")
      (node (ref "J2") (pin "8") (pinfunction "8_8") (pintype "passive"))
      (node (ref "U1") (pin "38") (pinfunction "MTMS/GPIO42_38") (pintype "passive"))
    )
    (net (code "53") (name "/GPIO45") (class "Default")
      (node (ref "J2") (pin "5") (pinfunction "5_5") (pintype "passive"))
      (node (ref "U1") (pin "41") (pinfunction "GPIO45_41") (pintype "passive"))
    )
    (net (code "54") (name "/GPIO46") (class "Default")
      (node (ref "J2") (pin "4") (pinfunction "4_4") (pintype "passive"))
      (node (ref "U1") (pin "44") (pinfunction "GPIO46_44") (pintype "passive"))
    )
    (net (code "55") (name "/GPIO47") (class "Default")
      (node (ref "J2") (pin "23") (pinfunction "23_23") (pintype "passive"))
      (node (ref "U1") (pin "27") (pinfunction "GPIO47/SPICLK_P_DIFF/SUBSPICLK_P_DIFF_27") (pintype "passive"))
    )
    (net (code "56") (name "/GPIO48") (class "Default")
      (node (ref "J2") (pin "22") (pinfunction "22_22") (pintype "passive"))
      (node (ref "U1") (pin "30") (pinfunction "GPIO48/SPICLK_N_DIFF/SUBSPICLK_N_DIFF_30") (pintype "passive"))
    )
    (net (code "57") (name "/RTS FTDI") (class "Default")
      (node (ref "Q2") (pin "3") (pinfunction "C_3") (pintype "passive"))
      (node (ref "U2") (pin "19") (pinfunction "~{RTS}_19") (pintype "passive"))
    )
    (net (code "58") (name "/RXD FTDI") (class "Default")
      (node (ref "R16") (pin "1") (pinfunction "1_1") (pintype "passive"))
      (node (ref "U2") (pin "1") (pinfunction "RXD_1") (pintype "passive"))
    )
    (net (code "59") (name "/SCK{slash}SCL") (class "Default")
      (node (ref "R30") (pin "1") (pinfunction "1_1") (pintype "passive"))
      (node (ref "R36") (pin "2") (pinfunction "2_2") (pintype "passive"))
      (node (ref "U3") (pin "4") (pinfunction "SCK/SCL_4") (pintype "passive"))
      (node (ref "U4") (pin "3") (pinfunction "SCL_3") (pintype "passive"))
    )
    (net (code "60") (name "/SDI{slash}SDA") (class "Default")
      (node (ref "R31") (pin "1") (pinfunction "1_1") (pintype "passive"))
      (node (ref "R35") (pin "2") (pinfunction "2_2") (pintype "passive"))
      (node (ref "U3") (pin "3") (pinfunction "SDI/SDA_3") (pintype "passive"))
      (node (ref "U4") (pin "4") (pinfunction "TX/SDA_4") (pintype "passive"))
    )
    (net (code "61") (name "/SDO{slash}ADR") (class "Default")
      (node (ref "R29") (pin "1") (pinfunction "1_1") (pintype "passive"))
      (node (ref "U3") (pin "5") (pinfunction "SDO/ADR_5") (pintype "passive"))
    )
    (net (code "62") (name "/TXD FTDI") (class "Default")
      (node (ref "R18") (pin "1") (pinfunction "1_1") (pintype "passive"))
      (node (ref "U2") (pin "17") (pinfunction "TXD_17") (pintype "passive"))
    )
    (net (code "63") (name "/U0RXD") (class "Default")
      (node (ref "R18") (pin "2") (pinfunction "2_2") (pintype "passive"))
      (node (ref "U1") (pin "40") (pinfunction "U0RXD/GPIO44/CLK_OUT2_40") (pintype "passive"))
    )
    (net (code "64") (name "/U0TXD") (class "Default")
      (node (ref "R16") (pin "2") (pinfunction "2_2") (pintype "passive"))
      (node (ref "U1") (pin "39") (pinfunction "U0TXD/GPIO43/CLK_OUT1_39") (pintype "passive"))
    )
    (net (code "65") (name "/VBUS SENSE") (class "Default")
      (node (ref "R10") (pin "1") (pinfunction "1_1") (pintype "passive"))
      (node (ref "R11") (pin "1") (pinfunction "1_1") (pintype "passive"))
      (node (ref "U2") (pin "16") (pinfunction "CBUS3_16") (pintype "passive"))
    )
    (net (code "66") (name "12V") (class "Default")
      (node (ref "C21") (pin "2") (pinfunction "_2_2") (pintype "passive"))
      (node (ref "C22") (pin "2") (pinfunction "_2_2") (pintype "passive"))
      (node (ref "C23") (pin "2") (pinfunction "_2_2") (pintype "passive"))
      (node (ref "C24") (pin "2") (pinfunction "_2_2") (pintype "passive"))
      (node (ref "C25") (pin "2") (pinfunction "_2_2") (pintype "passive"))
      (node (ref "C26") (pin "2") (pinfunction "_2_2") (pintype "passive"))
      (node (ref "C27") (pin "2") (pinfunction "_2_2") (pintype "passive"))
      (node (ref "D9") (pin "2") (pinfunction "2_2") (pintype "passive"))
      (node (ref "R33") (pin "2") (pinfunction "2_2") (pintype "passive"))
      (node (ref "U4") (pin "10") (pinfunction "VDD12_10") (pintype "passive"))
    )
    (net (code "67") (name "GND") (class "Default")
      (node (ref "C1") (pin "2") (pinfunction "_2_2") (pintype "passive"))
      (node (ref "C10") (pin "1") (pinfunction "1_1") (pintype "passive"))
      (node (ref "C11") (pin "1") (pinfunction "1_1") (pintype "passive"))
      (node (ref "C12") (pin "2") (pinfunction "_2_2") (pintype "passive"))
      (node (ref "C13") (pin "1") (pinfunction "1_1") (pintype "passive"))
      (node (ref "C14") (pin "1") (pinfunction "1_1") (pintype "passive"))
      (node (ref "C15") (pin "1") (pinfunction "1_1") (pintype "passive"))
      (node (ref "C16") (pin "1") (pinfunction "1_1") (pintype "passive"))
      (node (ref "C17") (pin "1") (pinfunction "1_1") (pintype "passive"))
      (node (ref "C18") (pin "1") (pinfunction "1_1") (pintype "passive"))
      (node (ref "C19") (pin "1") (pinfunction "1_1") (pintype "passive"))
      (node (ref "C2") (pin "1") (pinfunction "1_1") (pintype "passive"))
      (node (ref "C20") (pin "1") (pinfunction "1_1") (pintype "passive"))
      (node (ref "C21") (pin "1") (pinfunction "1_1") (pintype "passive"))
      (node (ref "C22") (pin "1") (pinfunction "1_1") (pintype "passive"))
      (node (ref "C23") (pin "1") (pinfunction "1_1") (pintype "passive"))
      (node (ref "C25") (pin "1") (pinfunction "1_1") (pintype "passive"))
      (node (ref "C26") (pin "1") (pinfunction "1_1") (pintype "passive"))
      (node (ref "C27") (pin "1") (pinfunction "1_1") (pintype "passive"))
      (node (ref "C28") (pin "1") (pinfunction "1_1") (pintype "passive"))
      (node (ref "C29") (pin "1") (pinfunction "1_1") (pintype "passive"))
      (node (ref "C3") (pin "1") (pinfunction "1_1") (pintype "passive"))
      (node (ref "C30") (pin "1") (pinfunction "1_1") (pintype "passive"))
      (node (ref "C4") (pin "1") (pinfunction "1_1") (pintype "passive"))
      (node (ref "C5") (pin "1") (pinfunction "1_1") (pintype "passive"))
      (node (ref "C6") (pin "1") (pinfunction "1_1") (pintype "passive"))
      (node (ref "C7") (pin "1") (pinfunction "1_1") (pintype "passive"))
      (node (ref "C8") (pin "1") (pinfunction "1_1") (pintype "passive"))
      (node (ref "C9") (pin "1") (pinfunction "1_1") (pintype "passive"))
      (node (ref "D1") (pin "2") (pinfunction "2_2") (pintype "passive"))
      (node (ref "D2") (pin "2") (pinfunction "2_2") (pintype "passive"))
      (node (ref "D3") (pin "2") (pinfunction "2_2") (pintype "passive"))
      (node (ref "D4") (pin "2") (pinfunction "2_2") (pintype "passive"))
      (node (ref "D5") (pin "2") (pinfunction "2_2") (pintype "passive"))
      (node (ref "D6") (pin "2") (pinfunction "2_2") (pintype "passive"))
      (node (ref "D7") (pin "1") (pinfunction "1_1") (pintype "passive"))
      (node (ref "J1") (pin "1") (pinfunction "1_1") (pintype "passive"))
      (node (ref "J1") (pin "23") (pinfunction "23_23") (pintype "passive"))
      (node (ref "J3") (pin "A1B12") (pinfunction "GND_A1B12_A1B12") (pintype "passive"))
      (node (ref "J3") (pin "B1A12") (pinfunction "GND_B1A12_B1A12") (pintype "passive"))
      (node (ref "J3") (pin "S1") (pinfunction "SHIELD__1_S1") (pintype "passive"))
      (node (ref "J3") (pin "S2") (pinfunction "SHILED_2_S2") (pintype "passive"))
      (node (ref "J3") (pin "S3") (pinfunction "SHILED_3_S3") (pintype "passive"))
      (node (ref "J3") (pin "S4") (pinfunction "SHIELD_4_S4") (pintype "passive"))
      (node (ref "J4") (pin "A1B12") (pinfunction "GND_A1B12_A1B12") (pintype "passive"))
      (node (ref "J4") (pin "B1A12") (pinfunction "GND_B1A12_B1A12") (pintype "passive"))
      (node (ref "J4") (pin "S1") (pinfunction "SHIELD__1_S1") (pintype "passive"))
      (node (ref "J4") (pin "S2") (pinfunction "SHILED_2_S2") (pintype "passive"))
      (node (ref "J4") (pin "S3") (pinfunction "SHILED_3_S3") (pintype "passive"))
      (node (ref "J4") (pin "S4") (pinfunction "SHIELD_4_S4") (pintype "passive"))
      (node (ref "Q3") (pin "3") (pinfunction "3_3") (pintype "passive"))
      (node (ref "R11") (pin "2") (pinfunction "2_2") (pintype "passive"))
      (node (ref "R12") (pin "2") (pinfunction "2_2") (pintype "passive"))
      (node (ref "R13") (pin "2") (pinfunction "2_2") (pintype "passive"))
      (node (ref "R34") (pin "1") (pinfunction "1_1") (pintype "passive"))
      (node (ref "R37") (pin "1") (pinfunction "1_1") (pintype "passive"))
      (node (ref "R39") (pin "1") (pinfunction "1_1") (pintype "passive"))
      (node (ref "R41") (pin "1") (pinfunction "1_1") (pintype "passive"))
      (node (ref "R42") (pin "1") (pinfunction "1_1") (pintype "passive"))
      (node (ref "R43") (pin "1") (pinfunction "1_1") (pintype "passive"))
      (node (ref "R7") (pin "1") (pinfunction "1_1") (pintype "passive"))
      (node (ref "R8") (pin "2") (pinfunction "2_2") (pintype "passive"))
      (node (ref "R9") (pin "2") (pinfunction "2_2") (pintype "passive"))
      (node (ref "SW1") (pin "3") (pinfunction "3_3") (pintype "passive"))
      (node (ref "SW1") (pin "4") (pinfunction "4_4") (pintype "passive"))
      (node (ref "SW2") (pin "3") (pinfunction "3_3") (pintype "passive"))
      (node (ref "SW2") (pin "4") (pinfunction "4_4") (pintype "passive"))
      (node (ref "U1") (pin "1") (pinfunction "GND_01_1") (pintype "passive"))
      (node (ref "U1") (pin "2") (pinfunction "GND_02_2") (pintype "passive"))
      (node (ref "U1") (pin "42") (pinfunction "GND_42") (pintype "passive"))
      (node (ref "U1") (pin "43") (pinfunction "GND_43") (pintype "passive"))
      (node (ref "U1") (pin "46") (pinfunction "GND_46_46") (pintype "passive"))
      (node (ref "U1") (pin "47") (pinfunction "GND_47_47") (pintype "passive"))
      (node (ref "U1") (pin "48") (pinfunction "GND_48_48") (pintype "passive"))
      (node (ref "U1") (pin "49") (pinfunction "GND_49_49") (pintype "passive"))
      (node (ref "U1") (pin "50") (pinfunction "GND_50_50") (pintype "passive"))
      (node (ref "U1") (pin "51") (pinfunction "GND_51_51") (pintype "passive"))
      (node (ref "U1") (pin "52") (pinfunction "GND_52_52") (pintype "passive"))
      (node (ref "U1") (pin "53") (pinfunction "GND_53_53") (pintype "passive"))
      (node (ref "U1") (pin "54") (pinfunction "GND_54_54") (pintype "passive"))
      (node (ref "U1") (pin "55") (pinfunction "GND_55_55") (pintype "passive"))
      (node (ref "U1") (pin "56") (pinfunction "GND_56_56") (pintype "passive"))
      (node (ref "U1") (pin "57") (pinfunction "GND_57_57") (pintype "passive"))
      (node (ref "U1") (pin "58") (pinfunction "GND_58_58") (pintype "passive"))
      (node (ref "U1") (pin "59") (pinfunction "GND_59_59") (pintype "passive"))
      (node (ref "U1") (pin "60") (pinfunction "GND_60_60") (pintype "passive"))
      (node (ref "U1") (pin "61") (pinfunction "GND_61_61") (pintype "passive"))
      (node (ref "U1") (pin "62") (pinfunction "GND_62_62") (pintype "passive"))
      (node (ref "U1") (pin "63") (pinfunction "GND_63_63") (pintype "passive"))
      (node (ref "U1") (pin "64") (pinfunction "GND_64_64") (pintype "passive"))
      (node (ref "U1") (pin "65") (pinfunction "GND_65_65") (pintype "passive"))
      (node (ref "U1") (pin "66") (pinfunction "GND_66_66") (pintype "passive"))
      (node (ref "U1") (pin "67") (pinfunction "GND_67_67") (pintype "passive"))
      (node (ref "U1") (pin "68") (pinfunction "GND_68_68") (pintype "passive"))
      (node (ref "U1") (pin "69") (pinfunction "GND_69_69") (pintype "passive"))
      (node (ref "U1") (pin "70") (pinfunction "GND_70_70") (pintype "passive"))
      (node (ref "U1") (pin "71") (pinfunction "GND_71_71") (pintype "passive"))
      (node (ref "U1") (pin "72") (pinfunction "GND_72_72") (pintype "passive"))
      (node (ref "U1") (pin "73") (pinfunction "GND_73_73") (pintype "passive"))
      (node (ref "U2") (pin "13") (pinfunction "GND_13") (pintype "passive"))
      (node (ref "U2") (pin "21") (pinfunction "GND_21") (pintype "passive"))
      (node (ref "U2") (pin "3") (pinfunction "GND_3") (pintype "passive"))
      (node (ref "U3") (pin "1") (pinfunction "GND_1") (pintype "passive"))
      (node (ref "U4") (pin "6") (pinfunction "GND_6") (pintype "passive"))
      (node (ref "U4") (pin "8") (pinfunction "PSEL_8") (pintype "passive"))
      (node (ref "U5") (pin "2") (pinfunction "GND_2") (pintype "passive"))
    )
    (net (code "68") (name "Net-(C2-_2)") (class "Default")
      (node (ref "C1") (pin "1") (pinfunction "1_1") (pintype "passive"))
      (node (ref "C2") (pin "2") (pinfunction "_2_2") (pintype "passive"))
      (node (ref "R1") (pin "1") (pinfunction "1_1") (pintype "passive"))
      (node (ref "R2") (pin "1") (pinfunction "1_1") (pintype "passive"))
      (node (ref "U2") (pin "12") (pinfunction "VCC_12") (pintype "passive"))
    )
    (net (code "69") (name "Net-(C15-_2)") (class "Default")
      (node (ref "C15") (pin "2") (pinfunction "_2_2") (pintype "passive"))
      (node (ref "R20") (pin "2") (pinfunction "2_2") (pintype "passive"))
    )
    (net (code "70") (name "Net-(C17-_2)") (class "Default")
      (node (ref "C17") (pin "2") (pinfunction "_2_2") (pintype "passive"))
      (node (ref "C18") (pin "2") (pinfunction "_2_2") (pintype "passive"))
      (node (ref "D8") (pin "1") (pinfunction "1_1") (pintype "passive"))
      (node (ref "U3") (pin "6") (pinfunction "VDDIO_6") (pintype "passive"))
      (node (ref "U3") (pin "8") (pinfunction "VDD_8") (pintype "passive"))
    )
    (net (code "71") (name "Net-(C19-_2)") (class "Default")
      (node (ref "C19") (pin "2") (pinfunction "_2_2") (pintype "passive"))
      (node (ref "C20") (pin "2") (pinfunction "_2_2") (pintype "passive"))
      (node (ref "R30") (pin "2") (pinfunction "2_2") (pintype "passive"))
      (node (ref "R31") (pin "2") (pinfunction "2_2") (pintype "passive"))
      (node (ref "U4") (pin "1") (pinfunction "VDD_1") (pintype "passive"))
    )
    (net (code "72") (name "Net-(D7-Pad2)") (class "Default")
      (node (ref "D7") (pin "2") (pinfunction "2_2") (pintype "passive"))
      (node (ref "R25") (pin "1") (pinfunction "1_1") (pintype "passive"))
    )
    (net (code "73") (name "Net-(D8-Pad2)") (class "Default")
      (node (ref "D8") (pin "2") (pinfunction "2_2") (pintype "passive"))
      (node (ref "R27") (pin "1") (pinfunction "1_1") (pintype "passive"))
    )
    (net (code "74") (name "Net-(H2-Pad2)") (class "Default")
      (node (ref "H2") (pin "2") (pinfunction "2_2") (pintype "passive"))
      (node (ref "R28") (pin "1") (pinfunction "1_1") (pintype "passive"))
    )
    (net (code "75") (name "Net-(H3-Pad2)") (class "Default")
      (node (ref "H3") (pin "2") (pinfunction "2_2") (pintype "passive"))
      (node (ref "R29") (pin "2") (pinfunction "2_2") (pintype "passive"))
    )
    (net (code "76") (name "Net-(J3-CC1)") (class "Default")
      (node (ref "J3") (pin "A5") (pinfunction "CC1_A5") (pintype "passive"))
      (node (ref "R9") (pin "1") (pinfunction "1_1") (pintype "passive"))
    )
    (net (code "77") (name "Net-(J3-CC2)") (class "Default")
      (node (ref "J3") (pin "B5") (pinfunction "CC2_B5") (pintype "passive"))
      (node (ref "R8") (pin "1") (pinfunction "1_1") (pintype "passive"))
    )
    (net (code "78") (name "Net-(J4-CC1)") (class "Default")
      (node (ref "J4") (pin "A5") (pinfunction "CC1_A5") (pintype "passive"))
      (node (ref "R13") (pin "1") (pinfunction "1_1") (pintype "passive"))
    )
    (net (code "79") (name "Net-(J4-CC2)") (class "Default")
      (node (ref "J4") (pin "B5") (pinfunction "CC2_B5") (pintype "passive"))
      (node (ref "R12") (pin "1") (pinfunction "1_1") (pintype "passive"))
    )
    (net (code "80") (name "Net-(LED1-Pad2)") (class "Default")
      (node (ref "LED1") (pin "2") (pinfunction "2_2") (pintype "passive"))
      (node (ref "R26") (pin "1") (pinfunction "1_1") (pintype "passive"))
    )
    (net (code "81") (name "Net-(Q1-B)") (class "Default")
      (node (ref "Q1") (pin "1") (pinfunction "B_1") (pintype "passive"))
      (node (ref "R14") (pin "2") (pinfunction "2_2") (pintype "passive"))
    )
    (net (code "82") (name "Net-(Q1-E)") (class "Default")
      (node (ref "Q1") (pin "2") (pinfunction "E_2") (pintype "passive"))
      (node (ref "R15") (pin "1") (pinfunction "1_1") (pintype "passive"))
    )
    (net (code "83") (name "Net-(Q2-B)") (class "Default")
      (node (ref "Q2") (pin "1") (pinfunction "B_1") (pintype "passive"))
      (node (ref "R15") (pin "2") (pinfunction "2_2") (pintype "passive"))
    )
    (net (code "84") (name "Net-(Q3-Pad1)") (class "Default")
      (node (ref "Q3") (pin "1") (pinfunction "1_1") (pintype "passive"))
      (node (ref "R38") (pin "1") (pinfunction "1_1") (pintype "passive"))
      (node (ref "R43") (pin "2") (pinfunction "2_2") (pintype "passive"))
    )
    (net (code "85") (name "Net-(Q3-Pad2)") (class "Default")
      (node (ref "Q3") (pin "2") (pinfunction "2_2") (pintype "passive"))
      (node (ref "R40") (pin "1") (pinfunction "1_1") (pintype "passive"))
      (node (ref "R42") (pin "2") (pinfunction "2_2") (pintype "passive"))
    )
    (net (code "86") (name "Net-(U2-CBUS0)") (class "Default")
      (node (ref "R7") (pin "2") (pinfunction "2_2") (pintype "passive"))
      (node (ref "U2") (pin "15") (pinfunction "CBUS0_15") (pintype "passive"))
    )
    (net (code "87") (name "Net-(U2-~{RESET})") (class "Default")
      (node (ref "R6") (pin "1") (pinfunction "1_1") (pintype "passive"))
      (node (ref "U2") (pin "11") (pinfunction "~{RESET}_11") (pintype "passive"))
    )
    (net (code "88") (name "Net-(U5-EN)") (class "Default")
      (node (ref "R32") (pin "1") (pinfunction "1_1") (pintype "passive"))
      (node (ref "U5") (pin "4") (pinfunction "EN_4") (pintype "passive"))
    )
    (net (code "89") (name "Net-(U5-FB)") (class "Default")
      (node (ref "C24") (pin "1") (pinfunction "1_1") (pintype "passive"))
      (node (ref "R33") (pin "1") (pinfunction "1_1") (pintype "passive"))
      (node (ref "R34") (pin "2") (pinfunction "2_2") (pintype "passive"))
      (node (ref "U5") (pin "3") (pinfunction "FB_3") (pintype "passive"))
    )
    (net (code "90") (name "Net-(U5-SW)") (class "Default")
      (node (ref "D9") (pin "1") (pinfunction "1_1") (pintype "passive"))
      (node (ref "L1") (pin "2") (pinfunction "2_2") (pintype "passive"))
      (node (ref "U5") (pin "1") (pinfunction "SW_1") (pintype "passive"))
    )
    (net (code "91") (name "Net-(U6-A)") (class "Default")
      (node (ref "R38") (pin "2") (pinfunction "2_2") (pintype "passive"))
      (node (ref "U6") (pin "1") (pinfunction "A_1") (pintype "passive"))
    )
    (net (code "92") (name "Net-(U6-B)") (class "Default")
      (node (ref "R41") (pin "2") (pinfunction "2_2") (pintype "passive"))
      (node (ref "U6") (pin "2") (pinfunction "B_2") (pintype "passive"))
    )
    (net (code "93") (name "Net-(U6-C)") (class "Default")
      (node (ref "R39") (pin "2") (pinfunction "2_2") (pintype "passive"))
      (node (ref "U6") (pin "3") (pinfunction "C_3") (pintype "passive"))
    )
    (net (code "94") (name "Net-(U6-D)") (class "Default")
      (node (ref "R37") (pin "2") (pinfunction "2_2") (pintype "passive"))
      (node (ref "U6") (pin "4") (pinfunction "D_4") (pintype "passive"))
    )
    (net (code "95") (name "unconnected-(J1-Pad24)") (class "Default")
      (node (ref "J1") (pin "24") (pinfunction "24_24") (pintype "passive+no_connect"))
    )
    (net (code "96") (name "unconnected-(J2-Pad2)") (class "Default")
      (node (ref "J2") (pin "2") (pinfunction "2_2") (pintype "passive"))
    )
    (net (code "97") (name "unconnected-(J2-Pad6)") (class "Default")
      (node (ref "J2") (pin "6") (pinfunction "6_6") (pintype "passive+no_connect"))
    )
    (net (code "98") (name "unconnected-(J2-Pad7)") (class "Default")
      (node (ref "J2") (pin "7") (pinfunction "7_7") (pintype "passive+no_connect"))
    )
    (net (code "99") (name "unconnected-(J2-Pad24)") (class "Default")
      (node (ref "J2") (pin "24") (pinfunction "24_24") (pintype "passive+no_connect"))
    )
    (net (code "100") (name "unconnected-(J3-SBU1-PadA8)") (class "Default")
      (node (ref "J3") (pin "A8") (pinfunction "SBU1_A8") (pintype "passive"))
    )
    (net (code "101") (name "unconnected-(J3-SBU2-PadB8)") (class "Default")
      (node (ref "J3") (pin "B8") (pinfunction "SBU2_B8") (pintype "passive"))
    )
    (net (code "102") (name "unconnected-(J3-VBUS_B4A9-PadB4A9)") (class "Default")
      (node (ref "J3") (pin "B4A9") (pinfunction "VBUS_B4A9_B4A9") (pintype "passive"))
    )
    (net (code "103") (name "unconnected-(J4-SBU1-PadA8)") (class "Default")
      (node (ref "J4") (pin "A8") (pinfunction "SBU1_A8") (pintype "passive"))
    )
    (net (code "104") (name "unconnected-(J4-SBU2-PadB8)") (class "Default")
      (node (ref "J4") (pin "B8") (pinfunction "SBU2_B8") (pintype "passive"))
    )
    (net (code "105") (name "unconnected-(J4-VBUS_B4A9-PadB4A9)") (class "Default")
      (node (ref "J4") (pin "B4A9") (pinfunction "VBUS_B4A9_B4A9") (pintype "passive"))
    )
    (net (code "106") (name "unconnected-(LDO1-GND-Pad2)") (class "Default")
      (node (ref "LDO1") (pin "2") (pinfunction "GND_2") (pintype "power_in"))
    )
    (net (code "107") (name "unconnected-(LDO1-GND-Pad4)") (class "Default")
      (node (ref "LDO1") (pin "4") (pinfunction "GND_4") (pintype "power_in"))
    )
    (net (code "108") (name "unconnected-(R40-Pad2)") (class "Default")
      (node (ref "R40") (pin "2") (pinfunction "2_2") (pintype "passive"))
    )
    (net (code "109") (name "unconnected-(U2-CBUS1-Pad14)") (class "Default")
      (node (ref "U2") (pin "14") (pinfunction "CBUS1_14") (pintype "passive+no_connect"))
    )
    (net (code "110") (name "unconnected-(U2-CBUS2-Pad7)") (class "Default")
      (node (ref "U2") (pin "7") (pinfunction "CBUS2_7") (pintype "passive+no_connect"))
    )
    (net (code "111") (name "unconnected-(U2-~{CTS}-Pad6)") (class "Default")
      (node (ref "U2") (pin "6") (pinfunction "~{CTS}_6") (pintype "passive+no_connect"))
    )
    (net (code "112") (name "unconnected-(U2-~{DCD}-Pad5)") (class "Default")
      (node (ref "U2") (pin "5") (pinfunction "~{DCD}_5") (pintype "passive+no_connect"))
    )
    (net (code "113") (name "unconnected-(U2-~{DSR}-Pad4)") (class "Default")
      (node (ref "U2") (pin "4") (pinfunction "~{DSR}_4") (pintype "passive+no_connect"))
    )
    (net (code "114") (name "unconnected-(U2-~{RI}-Pad2)") (class "Default")
      (node (ref "U2") (pin "2") (pinfunction "~{RI}_2") (pintype "passive+no_connect"))
    )
    (net (code "115") (name "unconnected-(U4-INT-Pad7)") (class "Default")
      (node (ref "U4") (pin "7") (pinfunction "INT_7") (pintype "passive+no_connect"))
    )
    (net (code "116") (name "unconnected-(U4-PWM-Pad9)") (class "Default")
      (node (ref "U4") (pin "9") (pinfunction "PWM_9") (pintype "passive+no_connect"))
    )
    (net (code "117") (name "unconnected-(U4-PWM{slash}DIS-Pad5)") (class "Default")
      (node (ref "U4") (pin "5") (pinfunction "PWM/DIS_5") (pintype "passive+no_connect"))
    )
    (net (code "118") (name "unconnected-(U4-RX-Pad2)") (class "Default")
      (node (ref "U4") (pin "2") (pinfunction "RX_2") (pintype "passive+no_connect"))
    )
    (net (code "119") (name "unconnected-(U6-E-Pad5)") (class "Default")
      (node (ref "U6") (pin "5") (pinfunction "E_5") (pintype "passive+no_connect"))
    )
    (net (code "120") (name "unconnected-(U6-K-Pad10)") (class "Default")
      (node (ref "U6") (pin "10") (pinfunction "K_10") (pintype "passive+no_connect"))
    )
  )
)
